# PCB_VHDCI_breakout.net
KiCad netlist of a schematic drawn in Altium Designer
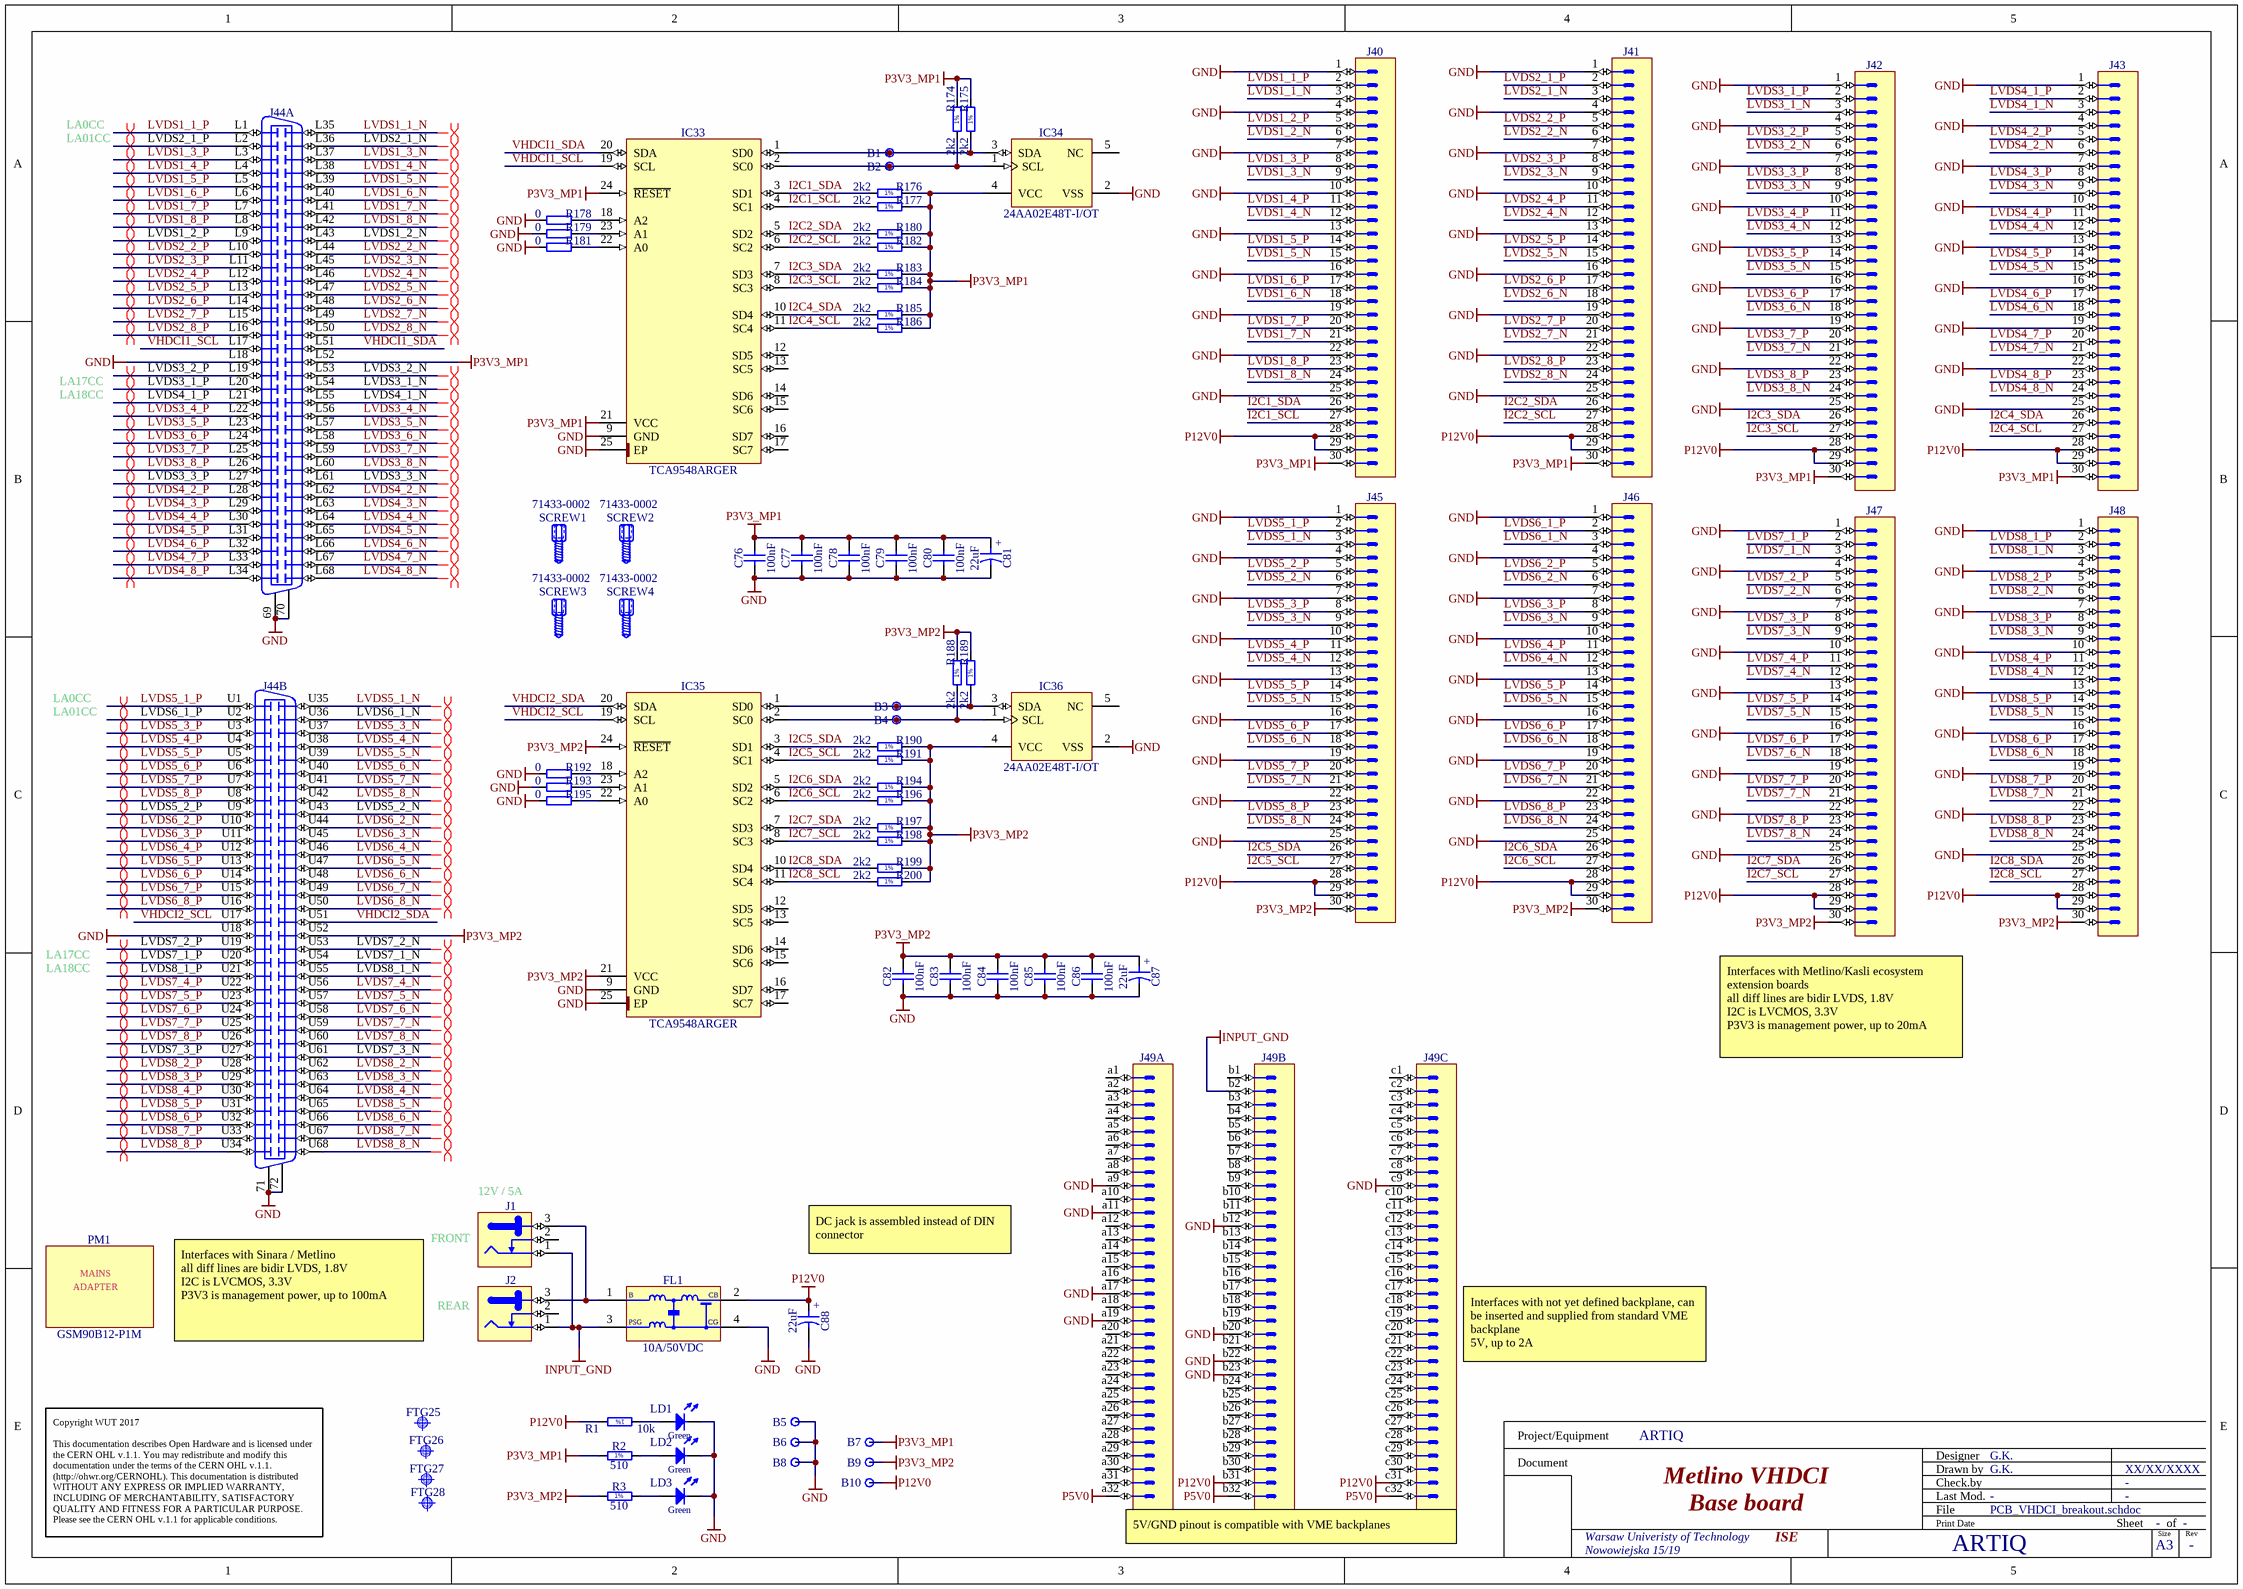
[diagram p0: PCB_VHDCI_breakout.schdoc]

(export (version "E")
  (design (tool "Eeschema 10.0.6"))
  (components
    (comp (ref "B1")
      (value "Plated Hole")
      (footprint "c130h60")
      (description "Single Terminal Socket")
      (fields (field (name "PART NUMBER") "PLATED_HOLE0.6_PAD1.3") (field (name "AUTHOR") "CERN DEM MR"))
      (libsource (lib "Eletro-mechanical") (part "Single Terminal Socket"))
    )
    (comp (ref "B2")
      (value "Plated Hole")
      (footprint "c130h60")
      (description "Single Terminal Socket")
      (fields (field (name "PART NUMBER") "PLATED_HOLE0.6_PAD1.3") (field (name "AUTHOR") "CERN DEM MR"))
      (libsource (lib "Eletro-mechanical") (part "Single Terminal Socket"))
    )
    (comp (ref "B3")
      (value "Plated Hole")
      (footprint "c130h60")
      (description "Single Terminal Socket")
      (fields (field (name "PART NUMBER") "PLATED_HOLE0.6_PAD1.3") (field (name "AUTHOR") "CERN DEM MR"))
      (libsource (lib "Eletro-mechanical") (part "Single Terminal Socket"))
    )
    (comp (ref "B4")
      (value "Plated Hole")
      (footprint "c130h60")
      (description "Single Terminal Socket")
      (fields (field (name "PART NUMBER") "PLATED_HOLE0.6_PAD1.3") (field (name "AUTHOR") "CERN DEM MR"))
      (libsource (lib "Eletro-mechanical") (part "Single Terminal Socket"))
    )
    (comp (ref "B5")
      (value "Plated Hole")
      (footprint "c130h60")
      (description "Single Terminal Socket")
      (fields (field (name "PART NUMBER") "PLATED_HOLE0.6_PAD1.3") (field (name "AUTHOR") "CERN DEM MR"))
      (libsource (lib "Eletro-mechanical") (part "Single Terminal Socket"))
    )
    (comp (ref "B6")
      (value "Plated Hole")
      (footprint "c130h60")
      (description "Single Terminal Socket")
      (fields (field (name "PART NUMBER") "PLATED_HOLE0.6_PAD1.3") (field (name "AUTHOR") "CERN DEM MR"))
      (libsource (lib "Eletro-mechanical") (part "Single Terminal Socket"))
    )
    (comp (ref "B7")
      (value "Plated Hole")
      (footprint "c130h60")
      (description "Single Terminal Socket")
      (fields (field (name "PART NUMBER") "PLATED_HOLE0.6_PAD1.3") (field (name "AUTHOR") "CERN DEM MR"))
      (libsource (lib "Eletro-mechanical") (part "Single Terminal Socket"))
    )
    (comp (ref "B8")
      (value "Plated Hole")
      (footprint "c130h60")
      (description "Single Terminal Socket")
      (fields (field (name "PART NUMBER") "PLATED_HOLE0.6_PAD1.3") (field (name "AUTHOR") "CERN DEM MR"))
      (libsource (lib "Eletro-mechanical") (part "Single Terminal Socket"))
    )
    (comp (ref "B9")
      (value "Plated Hole")
      (footprint "c130h60")
      (description "Single Terminal Socket")
      (fields (field (name "PART NUMBER") "PLATED_HOLE0.6_PAD1.3") (field (name "AUTHOR") "CERN DEM MR"))
      (libsource (lib "Eletro-mechanical") (part "Single Terminal Socket"))
    )
    (comp (ref "B10")
      (value "Plated Hole")
      (footprint "c130h60")
      (description "Single Terminal Socket")
      (fields (field (name "PART NUMBER") "PLATED_HOLE0.6_PAD1.3") (field (name "AUTHOR") "CERN DEM MR"))
      (libsource (lib "Eletro-mechanical") (part "Single Terminal Socket"))
    )
    (comp (ref "C76")
      (value "100nF")
      (footprint "CAPC1005X55N")
      (description "Non-polarised capacitor")
      (fields
        (field (name "PART NUMBER") "CC0402_100NF_16V_10%_X5R")
        (field (name "VOLTAGE") "16V")
        (field (name "AUTHOR") "CERN DEM JLC")
      )
      (libsource (lib "Capacitors") (part "Capacitor - non polarized"))
    )
    (comp (ref "C77")
      (value "100nF")
      (footprint "CAPC1005X55N")
      (description "Non-polarised capacitor")
      (fields
        (field (name "PART NUMBER") "CC0402_100NF_16V_10%_X5R")
        (field (name "VOLTAGE") "16V")
        (field (name "AUTHOR") "CERN DEM JLC")
      )
      (libsource (lib "Capacitors") (part "Capacitor - non polarized"))
    )
    (comp (ref "C78")
      (value "100nF")
      (footprint "CAPC1005X55N")
      (description "Non-polarised capacitor")
      (fields
        (field (name "PART NUMBER") "CC0402_100NF_16V_10%_X5R")
        (field (name "VOLTAGE") "16V")
        (field (name "AUTHOR") "CERN DEM JLC")
      )
      (libsource (lib "Capacitors") (part "Capacitor - non polarized"))
    )
    (comp (ref "C79")
      (value "100nF")
      (footprint "CAPC1005X55N")
      (description "Non-polarised capacitor")
      (fields
        (field (name "PART NUMBER") "CC0402_100NF_16V_10%_X5R")
        (field (name "VOLTAGE") "16V")
        (field (name "AUTHOR") "CERN DEM JLC")
      )
      (libsource (lib "Capacitors") (part "Capacitor - non polarized"))
    )
    (comp (ref "C80")
      (value "100nF")
      (footprint "CAPC1005X55N")
      (description "Non-polarised capacitor")
      (fields
        (field (name "PART NUMBER") "CC0402_100NF_16V_10%_X5R")
        (field (name "VOLTAGE") "16V")
        (field (name "AUTHOR") "CERN DEM JLC")
      )
      (libsource (lib "Capacitors") (part "Capacitor - non polarized"))
    )
    (comp (ref "C81")
      (value "22uF")
      (footprint "CAPAE530X540N")
      (description "Polarised capacitor")
      (fields
        (field (name "PART NUMBER") "CAE530-540_22UF_16V_20%")
        (field (name "VOLTAGE") "16V")
        (field (name "AUTHOR") "CERN DEM JLC")
      )
      (libsource (lib "Capacitors") (part "Capacitor - polarized"))
    )
    (comp (ref "C82")
      (value "100nF")
      (footprint "CAPC1005X55N")
      (description "Non-polarised capacitor")
      (fields
        (field (name "PART NUMBER") "CC0402_100NF_16V_10%_X5R")
        (field (name "VOLTAGE") "16V")
        (field (name "AUTHOR") "CERN DEM JLC")
      )
      (libsource (lib "Capacitors") (part "Capacitor - non polarized"))
    )
    (comp (ref "C83")
      (value "100nF")
      (footprint "CAPC1005X55N")
      (description "Non-polarised capacitor")
      (fields
        (field (name "PART NUMBER") "CC0402_100NF_16V_10%_X5R")
        (field (name "VOLTAGE") "16V")
        (field (name "AUTHOR") "CERN DEM JLC")
      )
      (libsource (lib "Capacitors") (part "Capacitor - non polarized"))
    )
    (comp (ref "C84")
      (value "100nF")
      (footprint "CAPC1005X55N")
      (description "Non-polarised capacitor")
      (fields
        (field (name "PART NUMBER") "CC0402_100NF_16V_10%_X5R")
        (field (name "VOLTAGE") "16V")
        (field (name "AUTHOR") "CERN DEM JLC")
      )
      (libsource (lib "Capacitors") (part "Capacitor - non polarized"))
    )
    (comp (ref "C85")
      (value "100nF")
      (footprint "CAPC1005X55N")
      (description "Non-polarised capacitor")
      (fields
        (field (name "PART NUMBER") "CC0402_100NF_16V_10%_X5R")
        (field (name "VOLTAGE") "16V")
        (field (name "AUTHOR") "CERN DEM JLC")
      )
      (libsource (lib "Capacitors") (part "Capacitor - non polarized"))
    )
    (comp (ref "C86")
      (value "100nF")
      (footprint "CAPC1005X55N")
      (description "Non-polarised capacitor")
      (fields
        (field (name "PART NUMBER") "CC0402_100NF_16V_10%_X5R")
        (field (name "VOLTAGE") "16V")
        (field (name "AUTHOR") "CERN DEM JLC")
      )
      (libsource (lib "Capacitors") (part "Capacitor - non polarized"))
    )
    (comp (ref "C87")
      (value "22uF")
      (footprint "CAPAE530X540N")
      (description "Polarised capacitor")
      (fields
        (field (name "PART NUMBER") "CAE530-540_22UF_16V_20%")
        (field (name "VOLTAGE") "16V")
        (field (name "AUTHOR") "CERN DEM JLC")
      )
      (libsource (lib "Capacitors") (part "Capacitor - polarized"))
    )
    (comp (ref "C88")
      (value "22uF")
      (footprint "CAPAE530X540N")
      (description "Polarised capacitor")
      (fields
        (field (name "PART NUMBER") "CAE530-540_22UF_16V_20%")
        (field (name "VOLTAGE") "16V")
        (field (name "AUTHOR") "CERN DEM JLC")
      )
      (libsource (lib "Capacitors") (part "Capacitor - polarized"))
    )
    (comp (ref "FL1")
      (value "10A/50VDC")
      (footprint "FIL_MURATA_BNX02")
      (description "Block Type EMIFIL (LC Combined)")
      (fields
        (field (name "PART NUMBER") "FIL_MURATA_BNX022-01L")
        (field (name "MANUFACTURER") "MURATA")
        (field (name "AUTHOR") "CERN DEM JLC")
      )
      (libsource (lib "Inductors & Transformers") (part "FIL_MURATA_BNX02"))
    )
    (comp (ref "FTG25")
      (value "Use only in PCB")
      (footprint "FIDUCIAL_TOP_C100-200")
      (description "Fiducial Target")
      (fields (field (name "PART NUMBER") "FIDUCIAL_TARGET_C100-200") (field (name "AUTHOR") "CERN DEM JLC"))
      (libsource (lib "Eletro-mechanical") (part "Fiducial Target"))
    )
    (comp (ref "FTG26")
      (value "Use only in PCB")
      (footprint "FIDUCIAL_TOP_S100-200")
      (description "Fiducial Target")
      (fields (field (name "PART NUMBER") "FIDUCIAL_TARGET_S100-200") (field (name "AUTHOR") "CERN DEM JLC"))
      (libsource (lib "Eletro-mechanical") (part "Fiducial Target"))
    )
    (comp (ref "FTG27")
      (value "Use only in PCB")
      (footprint "FIDUCIAL_TOP_S200-400")
      (description "Fiducial Target")
      (fields (field (name "PART NUMBER") "FIDUCIAL_TARGET_S200-400") (field (name "AUTHOR") "CERN DEM JLC"))
      (libsource (lib "Eletro-mechanical") (part "Fiducial Target"))
    )
    (comp (ref "FTG28")
      (value "Use only in PCB")
      (footprint "FIDUCIAL_TOP_S100-200")
      (description "Fiducial Target")
      (fields (field (name "PART NUMBER") "FIDUCIAL_TARGET_S100-200") (field (name "AUTHOR") "CERN DEM JLC"))
      (libsource (lib "Eletro-mechanical") (part "Fiducial Target"))
    )
    (comp (ref "IC33")
      (value "TCA9548ARGER")
      (footprint "QFN50P400X400X100-25N-S220")
      (description "Low Voltage 8-Channel I2C Switch With Reset")
      (fields (field (name "MANUFACTURER") "TEXAS INSTRUMENTS") (field (name "AUTHOR") "CERN DEM JLC"))
      (libsource (lib "ICs And Semiconductors") (part "TCA9548ARGER"))
    )
    (comp (ref "IC34")
      (value "24AA02E48T-I/OT")
      (footprint "SOT95P280X145-5N")
      (description "1.7V-5.5V, 2K I2C Serial EEPROM With EUI-48 Node Identity")
      (fields (field (name "MANUFACTURER") "MICROCHIP TECHNOLOGY") (field (name "AUTHOR") "CERN DEM MR"))
      (libsource (lib "ICs And Semiconductors") (part "24AA02E48T-I/OT"))
    )
    (comp (ref "IC35")
      (value "TCA9548ARGER")
      (footprint "QFN50P400X400X100-25N-S220")
      (description "Low Voltage 8-Channel I2C Switch With Reset")
      (fields (field (name "MANUFACTURER") "TEXAS INSTRUMENTS") (field (name "AUTHOR") "CERN DEM JLC"))
      (libsource (lib "ICs And Semiconductors") (part "TCA9548ARGER"))
    )
    (comp (ref "IC36")
      (value "24AA02E48T-I/OT")
      (footprint "SOT95P280X145-5N")
      (description "1.7V-5.5V, 2K I2C Serial EEPROM With EUI-48 Node Identity")
      (fields (field (name "MANUFACTURER") "MICROCHIP TECHNOLOGY") (field (name "AUTHOR") "CERN DEM MR"))
      (libsource (lib "ICs And Semiconductors") (part "24AA02E48T-I/OT"))
    )
    (comp (ref "J1")
      (value "Jack")
      (footprint "SWITCHCRAFT_L712RA")
      (description "24V /3. 5A, 2.1mm Diameter Pin, SMD DC Power Supply Connector With  Break Contact")
      (fields
        (field (name "PART NUMBER") "SWITCHCRAFT_L712RA")
        (field (name "MANUFACTURER") "SWITCHCRAFT")
        (field (name "AUTHOR") "GK")
      )
      (libsource (lib "LIBRARY_SCH") (part "CON_DC_5A_THT_RA"))
    )
    (comp (ref "J2")
      (value "Jack")
      (footprint "SWITCHCRAFT_L712RA")
      (description "24V /3. 5A, 2.1mm Diameter Pin, SMD DC Power Supply Connector With  Break Contact")
      (fields
        (field (name "PART NUMBER") "SWITCHCRAFT_L712RA")
        (field (name "MANUFACTURER") "SWITCHCRAFT")
        (field (name "AUTHOR") "GK")
      )
      (libsource (lib "LIBRARY_SCH") (part "CON_DC_5A_THT_RA"))
    )
    (comp (ref "J40")
      (value "~")
      (footprint "3M_N2530-6002RB")
      (description "Connector 30 Male")
      (fields
        (field (name "PART NUMBER") "3M_N2530-6002RB")
        (field (name "MANUFACTURER") "3M")
        (field (name "AUTHOR") "CERN DEM JLC")
      )
      (libsource (lib "Connectors") (part "Connector 30 Male"))
    )
    (comp (ref "J41")
      (value "~")
      (footprint "3M_N2530-6002RB")
      (description "Connector 30 Male")
      (fields
        (field (name "PART NUMBER") "3M_N2530-6002RB")
        (field (name "MANUFACTURER") "3M")
        (field (name "AUTHOR") "CERN DEM JLC")
      )
      (libsource (lib "Connectors") (part "Connector 30 Male"))
    )
    (comp (ref "J42")
      (value "~")
      (footprint "3M_N2530-6002RB")
      (description "Connector 30 Male")
      (fields
        (field (name "PART NUMBER") "3M_N2530-6002RB")
        (field (name "MANUFACTURER") "3M")
        (field (name "AUTHOR") "CERN DEM JLC")
      )
      (libsource (lib "Connectors") (part "Connector 30 Male"))
    )
    (comp (ref "J43")
      (value "~")
      (footprint "3M_N2530-6002RB")
      (description "Connector 30 Male")
      (fields
        (field (name "PART NUMBER") "3M_N2530-6002RB")
        (field (name "MANUFACTURER") "3M")
        (field (name "AUTHOR") "CERN DEM JLC")
      )
      (libsource (lib "Connectors") (part "Connector 30 Male"))
    )
    (comp (ref "J44")
      (value "VHDCI")
      (footprint "MOLEX_74337-0015")
      (description "Very High Density Cable Interconnect (VHDCI ) 2x68 Female")
      (fields
        (field (name "PART NUMBER") "Delivered by GK")
        (field (name "MANUFACTURER") "MOLEX")
        (field (name "AUTHOR") "CERN DEM JLC")
      )
      (libsource (lib "Connectors") (part "Connector VHDCI 2x68 Female"))
    )
    (comp (ref "J45")
      (value "~")
      (footprint "3M_N2530-6002RB")
      (description "Connector 30 Male")
      (fields
        (field (name "PART NUMBER") "3M_N2530-6002RB")
        (field (name "MANUFACTURER") "3M")
        (field (name "AUTHOR") "CERN DEM JLC")
      )
      (libsource (lib "Connectors") (part "Connector 30 Male"))
    )
    (comp (ref "J46")
      (value "~")
      (footprint "3M_N2530-6002RB")
      (description "Connector 30 Male")
      (fields
        (field (name "PART NUMBER") "3M_N2530-6002RB")
        (field (name "MANUFACTURER") "3M")
        (field (name "AUTHOR") "CERN DEM JLC")
      )
      (libsource (lib "Connectors") (part "Connector 30 Male"))
    )
    (comp (ref "J47")
      (value "~")
      (footprint "3M_N2530-6002RB")
      (description "Connector 30 Male")
      (fields
        (field (name "PART NUMBER") "3M_N2530-6002RB")
        (field (name "MANUFACTURER") "3M")
        (field (name "AUTHOR") "CERN DEM JLC")
      )
      (libsource (lib "Connectors") (part "Connector 30 Male"))
    )
    (comp (ref "J48")
      (value "~")
      (footprint "3M_N2530-6002RB")
      (description "Connector 30 Male")
      (fields
        (field (name "PART NUMBER") "3M_N2530-6002RB")
        (field (name "MANUFACTURER") "3M")
        (field (name "AUTHOR") "CERN DEM JLC")
      )
      (libsource (lib "Connectors") (part "Connector 30 Male"))
    )
    (comp (ref "J49")
      (value "DNP")
      (footprint "HARTING_09 03 196 2921")
      (description "Connector 96abc male (3x32)")
      (fields
        (field (name "PART NUMBER") "HARTING_09 03 196 2921")
        (field (name "MANUFACTURER") "HARTING")
        (field (name "AUTHOR") "CERN DEM JLC")
      )
      (libsource (lib "Connectors") (part "Connector 96abc male (3x32)"))
    )
    (comp (ref "LD1")
      (value "Green")
      (footprint "LED_KINGBRIGHT_KPH-1608CGCK")
      (description "LED Green 1C 2A")
      (fields
        (field (name "PART NUMBER") "LED_KINGBRIGHT_KPH-1608CGCK")
        (field (name "MANUFACTURER") "KINGBRIGHT")
        (field (name "AUTHOR") "CERN DEM JLC")
      )
      (libsource (lib "ICs And Semiconductors") (part "LED Green 1C 2A"))
    )
    (comp (ref "LD2")
      (value "Green")
      (footprint "LED_KINGBRIGHT_KPH-1608CGCK")
      (description "LED Green 1C 2A")
      (fields
        (field (name "PART NUMBER") "LED_KINGBRIGHT_KPH-1608CGCK")
        (field (name "MANUFACTURER") "KINGBRIGHT")
        (field (name "AUTHOR") "CERN DEM JLC")
      )
      (libsource (lib "ICs And Semiconductors") (part "LED Green 1C 2A"))
    )
    (comp (ref "LD3")
      (value "Green")
      (footprint "LED_KINGBRIGHT_KPH-1608CGCK")
      (description "LED Green 1C 2A")
      (fields
        (field (name "PART NUMBER") "LED_KINGBRIGHT_KPH-1608CGCK")
        (field (name "MANUFACTURER") "KINGBRIGHT")
        (field (name "AUTHOR") "CERN DEM JLC")
      )
      (libsource (lib "ICs And Semiconductors") (part "LED Green 1C 2A"))
    )
    (comp (ref "PM1")
      (value "GSM90B12-P1M")
      (footprint "DC_DC_GSM90B12-P1M")
      (description "90W  AC-DC  Medical Power Adaptor")
      (fields (field (name "MANUFACTURER") "MEAN WELL") (field (name "AUTHOR") "GK"))
      (libsource (lib "LIBRARY_SCH") (part "DC_DC_GSM90B12-P1M"))
    )
    (comp (ref "R1")
      (value "10k")
      (footprint "RESC1005X40N")
      (description "Resistor - 1%")
      (fields
        (field (name "PART NUMBER") "R0402_10K_1%_0.0625W_100PPM")
        (field (name "POWER") "0.0625W")
        (field (name "AUTHOR") "CERN DEM JLC")
      )
      (libsource (lib "Resistors") (part "Resistor - 1%"))
    )
    (comp (ref "R2")
      (value "510")
      (footprint "RESC1005X40N")
      (description "Resistor - 1%")
      (fields
        (field (name "PART NUMBER") "R0402_510R_1%_0.0625W_100PPM")
        (field (name "POWER") "0.0625W")
        (field (name "AUTHOR") "CERN DEM JLC")
      )
      (libsource (lib "Resistors") (part "Resistor - 1%"))
    )
    (comp (ref "R3")
      (value "510")
      (footprint "RESC1005X40N")
      (description "Resistor - 1%")
      (fields
        (field (name "PART NUMBER") "R0402_510R_1%_0.0625W_100PPM")
        (field (name "POWER") "0.0625W")
        (field (name "AUTHOR") "CERN DEM JLC")
      )
      (libsource (lib "Resistors") (part "Resistor - 1%"))
    )
    (comp (ref "R174")
      (value "2k2")
      (footprint "RESC1005X40N")
      (description "Resistor - 1%")
      (fields
        (field (name "PART NUMBER") "R0402_2K2_1%_0.0625W_100PPM")
        (field (name "POWER") "0.0625W")
        (field (name "AUTHOR") "CERN DEM JLC")
      )
      (libsource (lib "Resistors") (part "Resistor - 1%"))
    )
    (comp (ref "R175")
      (value "2k2")
      (footprint "RESC1005X40N")
      (description "Resistor - 1%")
      (fields
        (field (name "PART NUMBER") "R0402_2K2_1%_0.0625W_100PPM")
        (field (name "POWER") "0.0625W")
        (field (name "AUTHOR") "CERN DEM JLC")
      )
      (libsource (lib "Resistors") (part "Resistor - 1%"))
    )
    (comp (ref "R176")
      (value "2k2")
      (footprint "RESC1005X40N")
      (description "Resistor - 1%")
      (fields
        (field (name "PART NUMBER") "R0402_2K2_1%_0.0625W_100PPM")
        (field (name "POWER") "0.0625W")
        (field (name "AUTHOR") "CERN DEM JLC")
      )
      (libsource (lib "Resistors") (part "Resistor - 1%"))
    )
    (comp (ref "R177")
      (value "2k2")
      (footprint "RESC1005X40N")
      (description "Resistor - 1%")
      (fields
        (field (name "PART NUMBER") "R0402_2K2_1%_0.0625W_100PPM")
        (field (name "POWER") "0.0625W")
        (field (name "AUTHOR") "CERN DEM JLC")
      )
      (libsource (lib "Resistors") (part "Resistor - 1%"))
    )
    (comp (ref "R178")
      (value "0")
      (footprint "RESC1005X40N")
      (description "Resistor")
      (fields
        (field (name "PART NUMBER") "R0402_0R_JUMPER")
        (field (name "MANUFACTURER") "GENERIC")
        (field (name "AUTHOR") "CERN DEM JLC")
      )
      (libsource (lib "Resistors") (part "Resistor"))
    )
    (comp (ref "R179")
      (value "0")
      (footprint "RESC1005X40N")
      (description "Resistor")
      (fields
        (field (name "PART NUMBER") "R0402_0R_JUMPER")
        (field (name "MANUFACTURER") "GENERIC")
        (field (name "AUTHOR") "CERN DEM JLC")
      )
      (libsource (lib "Resistors") (part "Resistor"))
    )
    (comp (ref "R180")
      (value "2k2")
      (footprint "RESC1005X40N")
      (description "Resistor - 1%")
      (fields
        (field (name "PART NUMBER") "R0402_2K2_1%_0.0625W_100PPM")
        (field (name "POWER") "0.0625W")
        (field (name "AUTHOR") "CERN DEM JLC")
      )
      (libsource (lib "Resistors") (part "Resistor - 1%"))
    )
    (comp (ref "R181")
      (value "0")
      (footprint "RESC1005X40N")
      (description "Resistor")
      (fields
        (field (name "PART NUMBER") "R0402_0R_JUMPER")
        (field (name "MANUFACTURER") "GENERIC")
        (field (name "AUTHOR") "CERN DEM JLC")
      )
      (libsource (lib "Resistors") (part "Resistor"))
    )
    (comp (ref "R182")
      (value "2k2")
      (footprint "RESC1005X40N")
      (description "Resistor - 1%")
      (fields
        (field (name "PART NUMBER") "R0402_2K2_1%_0.0625W_100PPM")
        (field (name "POWER") "0.0625W")
        (field (name "AUTHOR") "CERN DEM JLC")
      )
      (libsource (lib "Resistors") (part "Resistor - 1%"))
    )
    (comp (ref "R183")
      (value "2k2")
      (footprint "RESC1005X40N")
      (description "Resistor - 1%")
      (fields
        (field (name "PART NUMBER") "R0402_2K2_1%_0.0625W_100PPM")
        (field (name "POWER") "0.0625W")
        (field (name "AUTHOR") "CERN DEM JLC")
      )
      (libsource (lib "Resistors") (part "Resistor - 1%"))
    )
    (comp (ref "R184")
      (value "2k2")
      (footprint "RESC1005X40N")
      (description "Resistor - 1%")
      (fields
        (field (name "PART NUMBER") "R0402_2K2_1%_0.0625W_100PPM")
        (field (name "POWER") "0.0625W")
        (field (name "AUTHOR") "CERN DEM JLC")
      )
      (libsource (lib "Resistors") (part "Resistor - 1%"))
    )
    (comp (ref "R185")
      (value "2k2")
      (footprint "RESC1005X40N")
      (description "Resistor - 1%")
      (fields
        (field (name "PART NUMBER") "R0402_2K2_1%_0.0625W_100PPM")
        (field (name "POWER") "0.0625W")
        (field (name "AUTHOR") "CERN DEM JLC")
      )
      (libsource (lib "Resistors") (part "Resistor - 1%"))
    )
    (comp (ref "R186")
      (value "2k2")
      (footprint "RESC1005X40N")
      (description "Resistor - 1%")
      (fields
        (field (name "PART NUMBER") "R0402_2K2_1%_0.0625W_100PPM")
        (field (name "POWER") "0.0625W")
        (field (name "AUTHOR") "CERN DEM JLC")
      )
      (libsource (lib "Resistors") (part "Resistor - 1%"))
    )
    (comp (ref "R188")
      (value "2k2")
      (footprint "RESC1005X40N")
      (description "Resistor - 1%")
      (fields
        (field (name "PART NUMBER") "R0402_2K2_1%_0.0625W_100PPM")
        (field (name "POWER") "0.0625W")
        (field (name "AUTHOR") "CERN DEM JLC")
      )
      (libsource (lib "Resistors") (part "Resistor - 1%"))
    )
    (comp (ref "R189")
      (value "2k2")
      (footprint "RESC1005X40N")
      (description "Resistor - 1%")
      (fields
        (field (name "PART NUMBER") "R0402_2K2_1%_0.0625W_100PPM")
        (field (name "POWER") "0.0625W")
        (field (name "AUTHOR") "CERN DEM JLC")
      )
      (libsource (lib "Resistors") (part "Resistor - 1%"))
    )
    (comp (ref "R190")
      (value "2k2")
      (footprint "RESC1005X40N")
      (description "Resistor - 1%")
      (fields
        (field (name "PART NUMBER") "R0402_2K2_1%_0.0625W_100PPM")
        (field (name "POWER") "0.0625W")
        (field (name "AUTHOR") "CERN DEM JLC")
      )
      (libsource (lib "Resistors") (part "Resistor - 1%"))
    )
    (comp (ref "R191")
      (value "2k2")
      (footprint "RESC1005X40N")
      (description "Resistor - 1%")
      (fields
        (field (name "PART NUMBER") "R0402_2K2_1%_0.0625W_100PPM")
        (field (name "POWER") "0.0625W")
        (field (name "AUTHOR") "CERN DEM JLC")
      )
      (libsource (lib "Resistors") (part "Resistor - 1%"))
    )
    (comp (ref "R192")
      (value "0")
      (footprint "RESC1005X40N")
      (description "Resistor")
      (fields
        (field (name "PART NUMBER") "R0402_0R_JUMPER")
        (field (name "MANUFACTURER") "GENERIC")
        (field (name "AUTHOR") "CERN DEM JLC")
      )
      (libsource (lib "Resistors") (part "Resistor"))
    )
    (comp (ref "R193")
      (value "0")
      (footprint "RESC1005X40N")
      (description "Resistor")
      (fields
        (field (name "PART NUMBER") "R0402_0R_JUMPER")
        (field (name "MANUFACTURER") "GENERIC")
        (field (name "AUTHOR") "CERN DEM JLC")
      )
      (libsource (lib "Resistors") (part "Resistor"))
    )
    (comp (ref "R194")
      (value "2k2")
      (footprint "RESC1005X40N")
      (description "Resistor - 1%")
      (fields
        (field (name "PART NUMBER") "R0402_2K2_1%_0.0625W_100PPM")
        (field (name "POWER") "0.0625W")
        (field (name "AUTHOR") "CERN DEM JLC")
      )
      (libsource (lib "Resistors") (part "Resistor - 1%"))
    )
    (comp (ref "R195")
      (value "0")
      (footprint "RESC1005X40N")
      (description "Resistor")
      (fields
        (field (name "PART NUMBER") "R0402_0R_JUMPER")
        (field (name "MANUFACTURER") "GENERIC")
        (field (name "AUTHOR") "CERN DEM JLC")
      )
      (libsource (lib "Resistors") (part "Resistor"))
    )
    (comp (ref "R196")
      (value "2k2")
      (footprint "RESC1005X40N")
      (description "Resistor - 1%")
      (fields
        (field (name "PART NUMBER") "R0402_2K2_1%_0.0625W_100PPM")
        (field (name "POWER") "0.0625W")
        (field (name "AUTHOR") "CERN DEM JLC")
      )
      (libsource (lib "Resistors") (part "Resistor - 1%"))
    )
    (comp (ref "R197")
      (value "2k2")
      (footprint "RESC1005X40N")
      (description "Resistor - 1%")
      (fields
        (field (name "PART NUMBER") "R0402_2K2_1%_0.0625W_100PPM")
        (field (name "POWER") "0.0625W")
        (field (name "AUTHOR") "CERN DEM JLC")
      )
      (libsource (lib "Resistors") (part "Resistor - 1%"))
    )
    (comp (ref "R198")
      (value "2k2")
      (footprint "RESC1005X40N")
      (description "Resistor - 1%")
      (fields
        (field (name "PART NUMBER") "R0402_2K2_1%_0.0625W_100PPM")
        (field (name "POWER") "0.0625W")
        (field (name "AUTHOR") "CERN DEM JLC")
      )
      (libsource (lib "Resistors") (part "Resistor - 1%"))
    )
    (comp (ref "R199")
      (value "2k2")
      (footprint "RESC1005X40N")
      (description "Resistor - 1%")
      (fields
        (field (name "PART NUMBER") "R0402_2K2_1%_0.0625W_100PPM")
        (field (name "POWER") "0.0625W")
        (field (name "AUTHOR") "CERN DEM JLC")
      )
      (libsource (lib "Resistors") (part "Resistor - 1%"))
    )
    (comp (ref "R200")
      (value "2k2")
      (footprint "RESC1005X40N")
      (description "Resistor - 1%")
      (fields
        (field (name "PART NUMBER") "R0402_2K2_1%_0.0625W_100PPM")
        (field (name "POWER") "0.0625W")
        (field (name "AUTHOR") "CERN DEM JLC")
      )
      (libsource (lib "Resistors") (part "Resistor - 1%"))
    )
    (comp (ref "SCREW1")
      (value "71433-0002")
      (footprint "MOLEX_71433-0002")
      (description "VHDCI Female Screw Lock")
      (fields
        (field (name "PART NUMBER") "MOLEX_71433-0002")
        (field (name "MANUFACTURER") "Molex")
        (field (name "AUTHOR") "GK")
      )
      (libsource (lib "LIBRARY_SCH") (part "MECH_VHDCI_screw_lock"))
    )
    (comp (ref "SCREW2")
      (value "71433-0002")
      (footprint "MOLEX_71433-0002")
      (description "VHDCI Female Screw Lock")
      (fields
        (field (name "PART NUMBER") "MOLEX_71433-0002")
        (field (name "MANUFACTURER") "Molex")
        (field (name "AUTHOR") "GK")
      )
      (libsource (lib "LIBRARY_SCH") (part "MECH_VHDCI_screw_lock"))
    )
    (comp (ref "SCREW3")
      (value "71433-0002")
      (footprint "MOLEX_71433-0002")
      (description "VHDCI Female Screw Lock")
      (fields
        (field (name "PART NUMBER") "MOLEX_71433-0002")
        (field (name "MANUFACTURER") "Molex")
        (field (name "AUTHOR") "GK")
      )
      (libsource (lib "LIBRARY_SCH") (part "MECH_VHDCI_screw_lock"))
    )
    (comp (ref "SCREW4")
      (value "71433-0002")
      (footprint "MOLEX_71433-0002")
      (description "VHDCI Female Screw Lock")
      (fields
        (field (name "PART NUMBER") "MOLEX_71433-0002")
        (field (name "MANUFACTURER") "Molex")
        (field (name "AUTHOR") "GK")
      )
      (libsource (lib "LIBRARY_SCH") (part "MECH_VHDCI_screw_lock"))
    )
  )
  (nets
    (net (code "1") (name "/I2C1_SCL") (class "Default")
      (node (ref "IC33") (pin "4") (pinfunction "SC1_4") (pintype "bidirectional"))
      (node (ref "J40") (pin "27") (pinfunction "27_27") (pintype "bidirectional"))
      (node (ref "R177") (pin "1") (pinfunction "1_1") (pintype "passive"))
    )
    (net (code "2") (name "/I2C1_SDA") (class "Default")
      (node (ref "IC33") (pin "3") (pinfunction "SD1_3") (pintype "bidirectional"))
      (node (ref "J40") (pin "26") (pinfunction "26_26") (pintype "bidirectional"))
      (node (ref "R176") (pin "1") (pinfunction "1_1") (pintype "passive"))
    )
    (net (code "3") (name "/I2C2_SCL") (class "Default")
      (node (ref "IC33") (pin "6") (pinfunction "SC2_6") (pintype "bidirectional"))
      (node (ref "J41") (pin "27") (pinfunction "27_27") (pintype "bidirectional"))
      (node (ref "R182") (pin "1") (pinfunction "1_1") (pintype "passive"))
    )
    (net (code "4") (name "/I2C2_SDA") (class "Default")
      (node (ref "IC33") (pin "5") (pinfunction "SD2_5") (pintype "bidirectional"))
      (node (ref "J41") (pin "26") (pinfunction "26_26") (pintype "bidirectional"))
      (node (ref "R180") (pin "1") (pinfunction "1_1") (pintype "passive"))
    )
    (net (code "5") (name "/I2C3_SCL") (class "Default")
      (node (ref "IC33") (pin "8") (pinfunction "SC3_8") (pintype "bidirectional"))
      (node (ref "J42") (pin "27") (pinfunction "27_27") (pintype "bidirectional"))
      (node (ref "R184") (pin "1") (pinfunction "1_1") (pintype "passive"))
    )
    (net (code "6") (name "/I2C3_SDA") (class "Default")
      (node (ref "IC33") (pin "7") (pinfunction "SD3_7") (pintype "bidirectional"))
      (node (ref "J42") (pin "26") (pinfunction "26_26") (pintype "bidirectional"))
      (node (ref "R183") (pin "1") (pinfunction "1_1") (pintype "passive"))
    )
    (net (code "7") (name "/I2C4_SCL") (class "Default")
      (node (ref "IC33") (pin "11") (pinfunction "SC4_11") (pintype "bidirectional"))
      (node (ref "J43") (pin "27") (pinfunction "27_27") (pintype "bidirectional"))
      (node (ref "R186") (pin "1") (pinfunction "1_1") (pintype "passive"))
    )
    (net (code "8") (name "/I2C4_SDA") (class "Default")
      (node (ref "IC33") (pin "10") (pinfunction "SD4_10") (pintype "bidirectional"))
      (node (ref "J43") (pin "26") (pinfunction "26_26") (pintype "bidirectional"))
      (node (ref "R185") (pin "1") (pinfunction "1_1") (pintype "passive"))
    )
    (net (code "9") (name "/I2C5_SCL") (class "Default")
      (node (ref "IC35") (pin "4") (pinfunction "SC1_4") (pintype "bidirectional"))
      (node (ref "J45") (pin "27") (pinfunction "27_27") (pintype "bidirectional"))
      (node (ref "R191") (pin "1") (pinfunction "1_1") (pintype "passive"))
    )
    (net (code "10") (name "/I2C5_SDA") (class "Default")
      (node (ref "IC35") (pin "3") (pinfunction "SD1_3") (pintype "bidirectional"))
      (node (ref "J45") (pin "26") (pinfunction "26_26") (pintype "bidirectional"))
      (node (ref "R190") (pin "1") (pinfunction "1_1") (pintype "passive"))
    )
    (net (code "11") (name "/I2C6_SCL") (class "Default")
      (node (ref "IC35") (pin "6") (pinfunction "SC2_6") (pintype "bidirectional"))
      (node (ref "J46") (pin "27") (pinfunction "27_27") (pintype "bidirectional"))
      (node (ref "R196") (pin "1") (pinfunction "1_1") (pintype "passive"))
    )
    (net (code "12") (name "/I2C6_SDA") (class "Default")
      (node (ref "IC35") (pin "5") (pinfunction "SD2_5") (pintype "bidirectional"))
      (node (ref "J46") (pin "26") (pinfunction "26_26") (pintype "bidirectional"))
      (node (ref "R194") (pin "1") (pinfunction "1_1") (pintype "passive"))
    )
    (net (code "13") (name "/I2C7_SCL") (class "Default")
      (node (ref "IC35") (pin "8") (pinfunction "SC3_8") (pintype "bidirectional"))
      (node (ref "J47") (pin "27") (pinfunction "27_27") (pintype "bidirectional"))
      (node (ref "R198") (pin "1") (pinfunction "1_1") (pintype "passive"))
    )
    (net (code "14") (name "/I2C7_SDA") (class "Default")
      (node (ref "IC35") (pin "7") (pinfunction "SD3_7") (pintype "bidirectional"))
      (node (ref "J47") (pin "26") (pinfunction "26_26") (pintype "bidirectional"))
      (node (ref "R197") (pin "1") (pinfunction "1_1") (pintype "passive"))
    )
    (net (code "15") (name "/I2C8_SCL") (class "Default")
      (node (ref "IC35") (pin "11") (pinfunction "SC4_11") (pintype "bidirectional"))
      (node (ref "J48") (pin "27") (pinfunction "27_27") (pintype "bidirectional"))
      (node (ref "R200") (pin "1") (pinfunction "1_1") (pintype "passive"))
    )
    (net (code "16") (name "/I2C8_SDA") (class "Default")
      (node (ref "IC35") (pin "10") (pinfunction "SD4_10") (pintype "bidirectional"))
      (node (ref "J48") (pin "26") (pinfunction "26_26") (pintype "bidirectional"))
      (node (ref "R199") (pin "1") (pinfunction "1_1") (pintype "passive"))
    )
    (net (code "17") (name "/LVDS1_1_N") (class "Default")
      (node (ref "J40") (pin "3") (pinfunction "3_3") (pintype "bidirectional"))
      (node (ref "J44") (pin "L35") (pinfunction "35_L35") (pintype "bidirectional"))
    )
    (net (code "18") (name "/LVDS1_1_P") (class "Default")
      (node (ref "J40") (pin "2") (pinfunction "2_2") (pintype "bidirectional"))
      (node (ref "J44") (pin "L1") (pinfunction "1_L1") (pintype "bidirectional"))
    )
    (net (code "19") (name "/LVDS1_2_N") (class "Default")
      (node (ref "J40") (pin "6") (pinfunction "6_6") (pintype "bidirectional"))
      (node (ref "J44") (pin "L43") (pinfunction "43_L43") (pintype "bidirectional"))
    )
    (net (code "20") (name "/LVDS1_2_P") (class "Default")
      (node (ref "J40") (pin "5") (pinfunction "5_5") (pintype "bidirectional"))
      (node (ref "J44") (pin "L9") (pinfunction "9_L9") (pintype "bidirectional"))
    )
    (net (code "21") (name "/LVDS1_3_N") (class "Default")
      (node (ref "J40") (pin "9") (pinfunction "9_9") (pintype "bidirectional"))
      (node (ref "J44") (pin "L37") (pinfunction "37_L37") (pintype "bidirectional"))
    )
    (net (code "22") (name "/LVDS1_3_P") (class "Default")
      (node (ref "J40") (pin "8") (pinfunction "8_8") (pintype "bidirectional"))
      (node (ref "J44") (pin "L3") (pinfunction "3_L3") (pintype "bidirectional"))
    )
    (net (code "23") (name "/LVDS1_4_N") (class "Default")
      (node (ref "J40") (pin "12") (pinfunction "12_12") (pintype "bidirectional"))
      (node (ref "J44") (pin "L38") (pinfunction "38_L38") (pintype "bidirectional"))
    )
    (net (code "24") (name "/LVDS1_4_P") (class "Default")
      (node (ref "J40") (pin "11") (pinfunction "11_11") (pintype "bidirectional"))
      (node (ref "J44") (pin "L4") (pinfunction "4_L4") (pintype "bidirectional"))
    )
    (net (code "25") (name "/LVDS1_5_N") (class "Default")
      (node (ref "J40") (pin "15") (pinfunction "15_15") (pintype "bidirectional"))
      (node (ref "J44") (pin "L39") (pinfunction "39_L39") (pintype "bidirectional"))
    )
    (net (code "26") (name "/LVDS1_5_P") (class "Default")
      (node (ref "J40") (pin "14") (pinfunction "14_14") (pintype "bidirectional"))
      (node (ref "J44") (pin "L5") (pinfunction "5_L5") (pintype "bidirectional"))
    )
    (net (code "27") (name "/LVDS1_6_N") (class "Default")
      (node (ref "J40") (pin "18") (pinfunction "18_18") (pintype "bidirectional"))
      (node (ref "J44") (pin "L40") (pinfunction "40_L40") (pintype "bidirectional"))
    )
    (net (code "28") (name "/LVDS1_6_P") (class "Default")
      (node (ref "J40") (pin "17") (pinfunction "17_17") (pintype "bidirectional"))
      (node (ref "J44") (pin "L6") (pinfunction "6_L6") (pintype "bidirectional"))
    )
    (net (code "29") (name "/LVDS1_7_N") (class "Default")
      (node (ref "J40") (pin "21") (pinfunction "21_21") (pintype "bidirectional"))
      (node (ref "J44") (pin "L41") (pinfunction "41_L41") (pintype "bidirectional"))
    )
    (net (code "30") (name "/LVDS1_7_P") (class "Default")
      (node (ref "J40") (pin "20") (pinfunction "20_20") (pintype "bidirectional"))
      (node (ref "J44") (pin "L7") (pinfunction "7_L7") (pintype "bidirectional"))
    )
    (net (code "31") (name "/LVDS1_8_N") (class "Default")
      (node (ref "J40") (pin "24") (pinfunction "24_24") (pintype "bidirectional"))
      (node (ref "J44") (pin "L42") (pinfunction "42_L42") (pintype "bidirectional"))
    )
    (net (code "32") (name "/LVDS1_8_P") (class "Default")
      (node (ref "J40") (pin "23") (pinfunction "23_23") (pintype "bidirectional"))
      (node (ref "J44") (pin "L8") (pinfunction "8_L8") (pintype "bidirectional"))
    )
    (net (code "33") (name "/LVDS2_1_N") (class "Default")
      (node (ref "J41") (pin "3") (pinfunction "3_3") (pintype "bidirectional"))
      (node (ref "J44") (pin "L36") (pinfunction "36_L36") (pintype "bidirectional"))
    )
    (net (code "34") (name "/LVDS2_1_P") (class "Default")
      (node (ref "J41") (pin "2") (pinfunction "2_2") (pintype "bidirectional"))
      (node (ref "J44") (pin "L2") (pinfunction "2_L2") (pintype "bidirectional"))
    )
    (net (code "35") (name "/LVDS2_2_N") (class "Default")
      (node (ref "J41") (pin "6") (pinfunction "6_6") (pintype "bidirectional"))
      (node (ref "J44") (pin "L44") (pinfunction "44_L44") (pintype "bidirectional"))
    )
    (net (code "36") (name "/LVDS2_2_P") (class "Default")
      (node (ref "J41") (pin "5") (pinfunction "5_5") (pintype "bidirectional"))
      (node (ref "J44") (pin "L10") (pinfunction "10_L10") (pintype "bidirectional"))
    )
    (net (code "37") (name "/LVDS2_3_N") (class "Default")
      (node (ref "J41") (pin "9") (pinfunction "9_9") (pintype "bidirectional"))
      (node (ref "J44") (pin "L45") (pinfunction "45_L45") (pintype "bidirectional"))
    )
    (net (code "38") (name "/LVDS2_3_P") (class "Default")
      (node (ref "J41") (pin "8") (pinfunction "8_8") (pintype "bidirectional"))
      (node (ref "J44") (pin "L11") (pinfunction "11_L11") (pintype "bidirectional"))
    )
    (net (code "39") (name "/LVDS2_4_N") (class "Default")
      (node (ref "J41") (pin "12") (pinfunction "12_12") (pintype "bidirectional"))
      (node (ref "J44") (pin "L46") (pinfunction "46_L46") (pintype "bidirectional"))
    )
    (net (code "40") (name "/LVDS2_4_P") (class "Default")
      (node (ref "J41") (pin "11") (pinfunction "11_11") (pintype "bidirectional"))
      (node (ref "J44") (pin "L12") (pinfunction "12_L12") (pintype "bidirectional"))
    )
    (net (code "41") (name "/LVDS2_5_N") (class "Default")
      (node (ref "J41") (pin "15") (pinfunction "15_15") (pintype "bidirectional"))
      (node (ref "J44") (pin "L47") (pinfunction "47_L47") (pintype "bidirectional"))
    )
    (net (code "42") (name "/LVDS2_5_P") (class "Default")
      (node (ref "J41") (pin "14") (pinfunction "14_14") (pintype "bidirectional"))
      (node (ref "J44") (pin "L13") (pinfunction "13_L13") (pintype "bidirectional"))
    )
    (net (code "43") (name "/LVDS2_6_N") (class "Default")
      (node (ref "J41") (pin "18") (pinfunction "18_18") (pintype "bidirectional"))
      (node (ref "J44") (pin "L48") (pinfunction "48_L48") (pintype "bidirectional"))
    )
    (net (code "44") (name "/LVDS2_6_P") (class "Default")
      (node (ref "J41") (pin "17") (pinfunction "17_17") (pintype "bidirectional"))
      (node (ref "J44") (pin "L14") (pinfunction "14_L14") (pintype "bidirectional"))
    )
    (net (code "45") (name "/LVDS2_7_N") (class "Default")
      (node (ref "J41") (pin "21") (pinfunction "21_21") (pintype "bidirectional"))
      (node (ref "J44") (pin "L49") (pinfunction "49_L49") (pintype "bidirectional"))
    )
    (net (code "46") (name "/LVDS2_7_P") (class "Default")
      (node (ref "J41") (pin "20") (pinfunction "20_20") (pintype "bidirectional"))
      (node (ref "J44") (pin "L15") (pinfunction "15_L15") (pintype "bidirectional"))
    )
    (net (code "47") (name "/LVDS2_8_N") (class "Default")
      (node (ref "J41") (pin "24") (pinfunction "24_24") (pintype "bidirectional"))
      (node (ref "J44") (pin "L50") (pinfunction "50_L50") (pintype "bidirectional"))
    )
    (net (code "48") (name "/LVDS2_8_P") (class "Default")
      (node (ref "J41") (pin "23") (pinfunction "23_23") (pintype "bidirectional"))
      (node (ref "J44") (pin "L16") (pinfunction "16_L16") (pintype "bidirectional"))
    )
    (net (code "49") (name "/LVDS3_1_N") (class "Default")
      (node (ref "J42") (pin "3") (pinfunction "3_3") (pintype "bidirectional"))
      (node (ref "J44") (pin "L54") (pinfunction "54_L54") (pintype "bidirectional"))
    )
    (net (code "50") (name "/LVDS3_1_P") (class "Default")
      (node (ref "J42") (pin "2") (pinfunction "2_2") (pintype "bidirectional"))
      (node (ref "J44") (pin "L20") (pinfunction "20_L20") (pintype "bidirectional"))
    )
    (net (code "51") (name "/LVDS3_2_N") (class "Default")
      (node (ref "J42") (pin "6") (pinfunction "6_6") (pintype "bidirectional"))
      (node (ref "J44") (pin "L53") (pinfunction "53_L53") (pintype "bidirectional"))
    )
    (net (code "52") (name "/LVDS3_2_P") (class "Default")
      (node (ref "J42") (pin "5") (pinfunction "5_5") (pintype "bidirectional"))
      (node (ref "J44") (pin "L19") (pinfunction "19_L19") (pintype "bidirectional"))
    )
    (net (code "53") (name "/LVDS3_3_N") (class "Default")
      (node (ref "J42") (pin "9") (pinfunction "9_9") (pintype "bidirectional"))
      (node (ref "J44") (pin "L61") (pinfunction "61_L61") (pintype "bidirectional"))
    )
    (net (code "54") (name "/LVDS3_3_P") (class "Default")
      (node (ref "J42") (pin "8") (pinfunction "8_8") (pintype "bidirectional"))
      (node (ref "J44") (pin "L27") (pinfunction "27_L27") (pintype "bidirectional"))
    )
    (net (code "55") (name "/LVDS3_4_N") (class "Default")
      (node (ref "J42") (pin "12") (pinfunction "12_12") (pintype "bidirectional"))
      (node (ref "J44") (pin "L56") (pinfunction "56_L56") (pintype "bidirectional"))
    )
    (net (code "56") (name "/LVDS3_4_P") (class "Default")
      (node (ref "J42") (pin "11") (pinfunction "11_11") (pintype "bidirectional"))
      (node (ref "J44") (pin "L22") (pinfunction "22_L22") (pintype "bidirectional"))
    )
    (net (code "57") (name "/LVDS3_5_N") (class "Default")
      (node (ref "J42") (pin "15") (pinfunction "15_15") (pintype "bidirectional"))
      (node (ref "J44") (pin "L57") (pinfunction "57_L57") (pintype "bidirectional"))
    )
    (net (code "58") (name "/LVDS3_5_P") (class "Default")
      (node (ref "J42") (pin "14") (pinfunction "14_14") (pintype "bidirectional"))
      (node (ref "J44") (pin "L23") (pinfunction "23_L23") (pintype "bidirectional"))
    )
    (net (code "59") (name "/LVDS3_6_N") (class "Default")
      (node (ref "J42") (pin "18") (pinfunction "18_18") (pintype "bidirectional"))
      (node (ref "J44") (pin "L58") (pinfunction "58_L58") (pintype "bidirectional"))
    )
    (net (code "60") (name "/LVDS3_6_P") (class "Default")
      (node (ref "J42") (pin "17") (pinfunction "17_17") (pintype "bidirectional"))
      (node (ref "J44") (pin "L24") (pinfunction "24_L24") (pintype "bidirectional"))
    )
    (net (code "61") (name "/LVDS3_7_N") (class "Default")
      (node (ref "J42") (pin "21") (pinfunction "21_21") (pintype "bidirectional"))
      (node (ref "J44") (pin "L59") (pinfunction "59_L59") (pintype "bidirectional"))
    )
    (net (code "62") (name "/LVDS3_7_P") (class "Default")
      (node (ref "J42") (pin "20") (pinfunction "20_20") (pintype "bidirectional"))
      (node (ref "J44") (pin "L25") (pinfunction "25_L25") (pintype "bidirectional"))
    )
    (net (code "63") (name "/LVDS3_8_N") (class "Default")
      (node (ref "J42") (pin "24") (pinfunction "24_24") (pintype "bidirectional"))
      (node (ref "J44") (pin "L60") (pinfunction "60_L60") (pintype "bidirectional"))
    )
    (net (code "64") (name "/LVDS3_8_P") (class "Default")
      (node (ref "J42") (pin "23") (pinfunction "23_23") (pintype "bidirectional"))
      (node (ref "J44") (pin "L26") (pinfunction "26_L26") (pintype "bidirectional"))
    )
    (net (code "65") (name "/LVDS4_1_N") (class "Default")
      (node (ref "J43") (pin "3") (pinfunction "3_3") (pintype "bidirectional"))
      (node (ref "J44") (pin "L55") (pinfunction "55_L55") (pintype "bidirectional"))
    )
    (net (code "66") (name "/LVDS4_1_P") (class "Default")
      (node (ref "J43") (pin "2") (pinfunction "2_2") (pintype "bidirectional"))
      (node (ref "J44") (pin "L21") (pinfunction "21_L21") (pintype "bidirectional"))
    )
    (net (code "67") (name "/LVDS4_2_N") (class "Default")
      (node (ref "J43") (pin "6") (pinfunction "6_6") (pintype "bidirectional"))
      (node (ref "J44") (pin "L62") (pinfunction "62_L62") (pintype "bidirectional"))
    )
    (net (code "68") (name "/LVDS4_2_P") (class "Default")
      (node (ref "J43") (pin "5") (pinfunction "5_5") (pintype "bidirectional"))
      (node (ref "J44") (pin "L28") (pinfunction "28_L28") (pintype "bidirectional"))
    )
    (net (code "69") (name "/LVDS4_3_N") (class "Default")
      (node (ref "J43") (pin "9") (pinfunction "9_9") (pintype "bidirectional"))
      (node (ref "J44") (pin "L63") (pinfunction "63_L63") (pintype "bidirectional"))
    )
    (net (code "70") (name "/LVDS4_3_P") (class "Default")
      (node (ref "J43") (pin "8") (pinfunction "8_8") (pintype "bidirectional"))
      (node (ref "J44") (pin "L29") (pinfunction "29_L29") (pintype "bidirectional"))
    )
    (net (code "71") (name "/LVDS4_4_N") (class "Default")
      (node (ref "J43") (pin "12") (pinfunction "12_12") (pintype "bidirectional"))
      (node (ref "J44") (pin "L64") (pinfunction "64_L64") (pintype "bidirectional"))
    )
    (net (code "72") (name "/LVDS4_4_P") (class "Default")
      (node (ref "J43") (pin "11") (pinfunction "11_11") (pintype "bidirectional"))
      (node (ref "J44") (pin "L30") (pinfunction "30_L30") (pintype "bidirectional"))
    )
    (net (code "73") (name "/LVDS4_5_N") (class "Default")
      (node (ref "J43") (pin "15") (pinfunction "15_15") (pintype "bidirectional"))
      (node (ref "J44") (pin "L65") (pinfunction "65_L65") (pintype "bidirectional"))
    )
    (net (code "74") (name "/LVDS4_5_P") (class "Default")
      (node (ref "J43") (pin "14") (pinfunction "14_14") (pintype "bidirectional"))
      (node (ref "J44") (pin "L31") (pinfunction "31_L31") (pintype "bidirectional"))
    )
    (net (code "75") (name "/LVDS4_6_N") (class "Default")
      (node (ref "J43") (pin "18") (pinfunction "18_18") (pintype "bidirectional"))
      (node (ref "J44") (pin "L66") (pinfunction "66_L66") (pintype "bidirectional"))
    )
    (net (code "76") (name "/LVDS4_6_P") (class "Default")
      (node (ref "J43") (pin "17") (pinfunction "17_17") (pintype "bidirectional"))
      (node (ref "J44") (pin "L32") (pinfunction "32_L32") (pintype "bidirectional"))
    )
    (net (code "77") (name "/LVDS4_7_N") (class "Default")
      (node (ref "J43") (pin "21") (pinfunction "21_21") (pintype "bidirectional"))
      (node (ref "J44") (pin "L67") (pinfunction "67_L67") (pintype "bidirectional"))
    )
    (net (code "78") (name "/LVDS4_7_P") (class "Default")
      (node (ref "J43") (pin "20") (pinfunction "20_20") (pintype "bidirectional"))
      (node (ref "J44") (pin "L33") (pinfunction "33_L33") (pintype "bidirectional"))
    )
    (net (code "79") (name "/LVDS4_8_N") (class "Default")
      (node (ref "J43") (pin "24") (pinfunction "24_24") (pintype "bidirectional"))
      (node (ref "J44") (pin "L68") (pinfunction "68_L68") (pintype "bidirectional"))
    )
    (net (code "80") (name "/LVDS4_8_P") (class "Default")
      (node (ref "J43") (pin "23") (pinfunction "23_23") (pintype "bidirectional"))
      (node (ref "J44") (pin "L34") (pinfunction "34_L34") (pintype "bidirectional"))
    )
    (net (code "81") (name "/LVDS5_1_N") (class "Default")
      (node (ref "J44") (pin "U35") (pinfunction "35_U35") (pintype "bidirectional"))
      (node (ref "J45") (pin "3") (pinfunction "3_3") (pintype "bidirectional"))
    )
    (net (code "82") (name "/LVDS5_1_P") (class "Default")
      (node (ref "J44") (pin "U1") (pinfunction "1_U1") (pintype "bidirectional"))
      (node (ref "J45") (pin "2") (pinfunction "2_2") (pintype "bidirectional"))
    )
    (net (code "83") (name "/LVDS5_2_N") (class "Default")
      (node (ref "J44") (pin "U43") (pinfunction "43_U43") (pintype "bidirectional"))
      (node (ref "J45") (pin "6") (pinfunction "6_6") (pintype "bidirectional"))
    )
    (net (code "84") (name "/LVDS5_2_P") (class "Default")
      (node (ref "J44") (pin "U9") (pinfunction "9_U9") (pintype "bidirectional"))
      (node (ref "J45") (pin "5") (pinfunction "5_5") (pintype "bidirectional"))
    )
    (net (code "85") (name "/LVDS5_3_N") (class "Default")
      (node (ref "J44") (pin "U37") (pinfunction "37_U37") (pintype "bidirectional"))
      (node (ref "J45") (pin "9") (pinfunction "9_9") (pintype "bidirectional"))
    )
    (net (code "86") (name "/LVDS5_3_P") (class "Default")
      (node (ref "J44") (pin "U3") (pinfunction "3_U3") (pintype "bidirectional"))
      (node (ref "J45") (pin "8") (pinfunction "8_8") (pintype "bidirectional"))
    )
    (net (code "87") (name "/LVDS5_4_N") (class "Default")
      (node (ref "J44") (pin "U38") (pinfunction "38_U38") (pintype "bidirectional"))
      (node (ref "J45") (pin "12") (pinfunction "12_12") (pintype "bidirectional"))
    )
    (net (code "88") (name "/LVDS5_4_P") (class "Default")
      (node (ref "J44") (pin "U4") (pinfunction "4_U4") (pintype "bidirectional"))
      (node (ref "J45") (pin "11") (pinfunction "11_11") (pintype "bidirectional"))
    )
    (net (code "89") (name "/LVDS5_5_N") (class "Default")
      (node (ref "J44") (pin "U39") (pinfunction "39_U39") (pintype "bidirectional"))
      (node (ref "J45") (pin "15") (pinfunction "15_15") (pintype "bidirectional"))
    )
    (net (code "90") (name "/LVDS5_5_P") (class "Default")
      (node (ref "J44") (pin "U5") (pinfunction "5_U5") (pintype "bidirectional"))
      (node (ref "J45") (pin "14") (pinfunction "14_14") (pintype "bidirectional"))
    )
    (net (code "91") (name "/LVDS5_6_N") (class "Default")
      (node (ref "J44") (pin "U40") (pinfunction "40_U40") (pintype "bidirectional"))
      (node (ref "J45") (pin "18") (pinfunction "18_18") (pintype "bidirectional"))
    )
    (net (code "92") (name "/LVDS5_6_P") (class "Default")
      (node (ref "J44") (pin "U6") (pinfunction "6_U6") (pintype "bidirectional"))
      (node (ref "J45") (pin "17") (pinfunction "17_17") (pintype "bidirectional"))
    )
    (net (code "93") (name "/LVDS5_7_N") (class "Default")
      (node (ref "J44") (pin "U41") (pinfunction "41_U41") (pintype "bidirectional"))
      (node (ref "J45") (pin "21") (pinfunction "21_21") (pintype "bidirectional"))
    )
    (net (code "94") (name "/LVDS5_7_P") (class "Default")
      (node (ref "J44") (pin "U7") (pinfunction "7_U7") (pintype "bidirectional"))
      (node (ref "J45") (pin "20") (pinfunction "20_20") (pintype "bidirectional"))
    )
    (net (code "95") (name "/LVDS5_8_N") (class "Default")
      (node (ref "J44") (pin "U42") (pinfunction "42_U42") (pintype "bidirectional"))
      (node (ref "J45") (pin "24") (pinfunction "24_24") (pintype "bidirectional"))
    )
    (net (code "96") (name "/LVDS5_8_P") (class "Default")
      (node (ref "J44") (pin "U8") (pinfunction "8_U8") (pintype "bidirectional"))
      (node (ref "J45") (pin "23") (pinfunction "23_23") (pintype "bidirectional"))
    )
    (net (code "97") (name "/LVDS6_1_N") (class "Default")
      (node (ref "J44") (pin "U36") (pinfunction "36_U36") (pintype "bidirectional"))
      (node (ref "J46") (pin "3") (pinfunction "3_3") (pintype "bidirectional"))
    )
    (net (code "98") (name "/LVDS6_1_P") (class "Default")
      (node (ref "J44") (pin "U2") (pinfunction "2_U2") (pintype "bidirectional"))
      (node (ref "J46") (pin "2") (pinfunction "2_2") (pintype "bidirectional"))
    )
    (net (code "99") (name "/LVDS6_2_N") (class "Default")
      (node (ref "J44") (pin "U44") (pinfunction "44_U44") (pintype "bidirectional"))
      (node (ref "J46") (pin "6") (pinfunction "6_6") (pintype "bidirectional"))
    )
    (net (code "100") (name "/LVDS6_2_P") (class "Default")
      (node (ref "J44") (pin "U10") (pinfunction "10_U10") (pintype "bidirectional"))
      (node (ref "J46") (pin "5") (pinfunction "5_5") (pintype "bidirectional"))
    )
    (net (code "101") (name "/LVDS6_3_N") (class "Default")
      (node (ref "J44") (pin "U45") (pinfunction "45_U45") (pintype "bidirectional"))
      (node (ref "J46") (pin "9") (pinfunction "9_9") (pintype "bidirectional"))
    )
    (net (code "102") (name "/LVDS6_3_P") (class "Default")
      (node (ref "J44") (pin "U11") (pinfunction "11_U11") (pintype "bidirectional"))
      (node (ref "J46") (pin "8") (pinfunction "8_8") (pintype "bidirectional"))
    )
    (net (code "103") (name "/LVDS6_4_N") (class "Default")
      (node (ref "J44") (pin "U46") (pinfunction "46_U46") (pintype "bidirectional"))
      (node (ref "J46") (pin "12") (pinfunction "12_12") (pintype "bidirectional"))
    )
    (net (code "104") (name "/LVDS6_4_P") (class "Default")
      (node (ref "J44") (pin "U12") (pinfunction "12_U12") (pintype "bidirectional"))
      (node (ref "J46") (pin "11") (pinfunction "11_11") (pintype "bidirectional"))
    )
    (net (code "105") (name "/LVDS6_5_N") (class "Default")
      (node (ref "J44") (pin "U47") (pinfunction "47_U47") (pintype "bidirectional"))
      (node (ref "J46") (pin "15") (pinfunction "15_15") (pintype "bidirectional"))
    )
    (net (code "106") (name "/LVDS6_5_P") (class "Default")
      (node (ref "J44") (pin "U13") (pinfunction "13_U13") (pintype "bidirectional"))
      (node (ref "J46") (pin "14") (pinfunction "14_14") (pintype "bidirectional"))
    )
    (net (code "107") (name "/LVDS6_6_N") (class "Default")
      (node (ref "J44") (pin "U48") (pinfunction "48_U48") (pintype "bidirectional"))
      (node (ref "J46") (pin "18") (pinfunction "18_18") (pintype "bidirectional"))
    )
    (net (code "108") (name "/LVDS6_6_P") (class "Default")
      (node (ref "J44") (pin "U14") (pinfunction "14_U14") (pintype "bidirectional"))
      (node (ref "J46") (pin "17") (pinfunction "17_17") (pintype "bidirectional"))
    )
    (net (code "109") (name "/LVDS6_7_N") (class "Default")
      (node (ref "J44") (pin "U49") (pinfunction "49_U49") (pintype "bidirectional"))
      (node (ref "J46") (pin "21") (pinfunction "21_21") (pintype "bidirectional"))
    )
    (net (code "110") (name "/LVDS6_7_P") (class "Default")
      (node (ref "J44") (pin "U15") (pinfunction "15_U15") (pintype "bidirectional"))
      (node (ref "J46") (pin "20") (pinfunction "20_20") (pintype "bidirectional"))
    )
    (net (code "111") (name "/LVDS6_8_N") (class "Default")
      (node (ref "J44") (pin "U50") (pinfunction "50_U50") (pintype "bidirectional"))
      (node (ref "J46") (pin "24") (pinfunction "24_24") (pintype "bidirectional"))
    )
    (net (code "112") (name "/LVDS6_8_P") (class "Default")
      (node (ref "J44") (pin "U16") (pinfunction "16_U16") (pintype "bidirectional"))
      (node (ref "J46") (pin "23") (pinfunction "23_23") (pintype "bidirectional"))
    )
    (net (code "113") (name "/LVDS7_1_N") (class "Default")
      (node (ref "J44") (pin "U54") (pinfunction "54_U54") (pintype "bidirectional"))
      (node (ref "J47") (pin "3") (pinfunction "3_3") (pintype "bidirectional"))
    )
    (net (code "114") (name "/LVDS7_1_P") (class "Default")
      (node (ref "J44") (pin "U20") (pinfunction "20_U20") (pintype "bidirectional"))
      (node (ref "J47") (pin "2") (pinfunction "2_2") (pintype "bidirectional"))
    )
    (net (code "115") (name "/LVDS7_2_N") (class "Default")
      (node (ref "J44") (pin "U53") (pinfunction "53_U53") (pintype "bidirectional"))
      (node (ref "J47") (pin "6") (pinfunction "6_6") (pintype "bidirectional"))
    )
    (net (code "116") (name "/LVDS7_2_P") (class "Default")
      (node (ref "J44") (pin "U19") (pinfunction "19_U19") (pintype "bidirectional"))
      (node (ref "J47") (pin "5") (pinfunction "5_5") (pintype "bidirectional"))
    )
    (net (code "117") (name "/LVDS7_3_N") (class "Default")
      (node (ref "J44") (pin "U61") (pinfunction "61_U61") (pintype "bidirectional"))
      (node (ref "J47") (pin "9") (pinfunction "9_9") (pintype "bidirectional"))
    )
    (net (code "118") (name "/LVDS7_3_P") (class "Default")
      (node (ref "J44") (pin "U27") (pinfunction "27_U27") (pintype "bidirectional"))
      (node (ref "J47") (pin "8") (pinfunction "8_8") (pintype "bidirectional"))
    )
    (net (code "119") (name "/LVDS7_4_N") (class "Default")
      (node (ref "J44") (pin "U56") (pinfunction "56_U56") (pintype "bidirectional"))
      (node (ref "J47") (pin "12") (pinfunction "12_12") (pintype "bidirectional"))
    )
    (net (code "120") (name "/LVDS7_4_P") (class "Default")
      (node (ref "J44") (pin "U22") (pinfunction "22_U22") (pintype "bidirectional"))
      (node (ref "J47") (pin "11") (pinfunction "11_11") (pintype "bidirectional"))
    )
    (net (code "121") (name "/LVDS7_5_N") (class "Default")
      (node (ref "J44") (pin "U57") (pinfunction "57_U57") (pintype "bidirectional"))
      (node (ref "J47") (pin "15") (pinfunction "15_15") (pintype "bidirectional"))
    )
    (net (code "122") (name "/LVDS7_5_P") (class "Default")
      (node (ref "J44") (pin "U23") (pinfunction "23_U23") (pintype "bidirectional"))
      (node (ref "J47") (pin "14") (pinfunction "14_14") (pintype "bidirectional"))
    )
    (net (code "123") (name "/LVDS7_6_N") (class "Default")
      (node (ref "J44") (pin "U58") (pinfunction "58_U58") (pintype "bidirectional"))
      (node (ref "J47") (pin "18") (pinfunction "18_18") (pintype "bidirectional"))
    )
    (net (code "124") (name "/LVDS7_6_P") (class "Default")
      (node (ref "J44") (pin "U24") (pinfunction "24_U24") (pintype "bidirectional"))
      (node (ref "J47") (pin "17") (pinfunction "17_17") (pintype "bidirectional"))
    )
    (net (code "125") (name "/LVDS7_7_N") (class "Default")
      (node (ref "J44") (pin "U59") (pinfunction "59_U59") (pintype "bidirectional"))
      (node (ref "J47") (pin "21") (pinfunction "21_21") (pintype "bidirectional"))
    )
    (net (code "126") (name "/LVDS7_7_P") (class "Default")
      (node (ref "J44") (pin "U25") (pinfunction "25_U25") (pintype "bidirectional"))
      (node (ref "J47") (pin "20") (pinfunction "20_20") (pintype "bidirectional"))
    )
    (net (code "127") (name "/LVDS7_8_N") (class "Default")
      (node (ref "J44") (pin "U60") (pinfunction "60_U60") (pintype "bidirectional"))
      (node (ref "J47") (pin "24") (pinfunction "24_24") (pintype "bidirectional"))
    )
    (net (code "128") (name "/LVDS7_8_P") (class "Default")
      (node (ref "J44") (pin "U26") (pinfunction "26_U26") (pintype "bidirectional"))
      (node (ref "J47") (pin "23") (pinfunction "23_23") (pintype "bidirectional"))
    )
    (net (code "129") (name "/LVDS8_1_N") (class "Default")
      (node (ref "J44") (pin "U55") (pinfunction "55_U55") (pintype "bidirectional"))
      (node (ref "J48") (pin "3") (pinfunction "3_3") (pintype "bidirectional"))
    )
    (net (code "130") (name "/LVDS8_1_P") (class "Default")
      (node (ref "J44") (pin "U21") (pinfunction "21_U21") (pintype "bidirectional"))
      (node (ref "J48") (pin "2") (pinfunction "2_2") (pintype "bidirectional"))
    )
    (net (code "131") (name "/LVDS8_2_N") (class "Default")
      (node (ref "J44") (pin "U62") (pinfunction "62_U62") (pintype "bidirectional"))
      (node (ref "J48") (pin "6") (pinfunction "6_6") (pintype "bidirectional"))
    )
    (net (code "132") (name "/LVDS8_2_P") (class "Default")
      (node (ref "J44") (pin "U28") (pinfunction "28_U28") (pintype "bidirectional"))
      (node (ref "J48") (pin "5") (pinfunction "5_5") (pintype "bidirectional"))
    )
    (net (code "133") (name "/LVDS8_3_N") (class "Default")
      (node (ref "J44") (pin "U63") (pinfunction "63_U63") (pintype "bidirectional"))
      (node (ref "J48") (pin "9") (pinfunction "9_9") (pintype "bidirectional"))
    )
    (net (code "134") (name "/LVDS8_3_P") (class "Default")
      (node (ref "J44") (pin "U29") (pinfunction "29_U29") (pintype "bidirectional"))
      (node (ref "J48") (pin "8") (pinfunction "8_8") (pintype "bidirectional"))
    )
    (net (code "135") (name "/LVDS8_4_N") (class "Default")
      (node (ref "J44") (pin "U64") (pinfunction "64_U64") (pintype "bidirectional"))
      (node (ref "J48") (pin "12") (pinfunction "12_12") (pintype "bidirectional"))
    )
    (net (code "136") (name "/LVDS8_4_P") (class "Default")
      (node (ref "J44") (pin "U30") (pinfunction "30_U30") (pintype "bidirectional"))
      (node (ref "J48") (pin "11") (pinfunction "11_11") (pintype "bidirectional"))
    )
    (net (code "137") (name "/LVDS8_5_N") (class "Default")
      (node (ref "J44") (pin "U65") (pinfunction "65_U65") (pintype "bidirectional"))
      (node (ref "J48") (pin "15") (pinfunction "15_15") (pintype "bidirectional"))
    )
    (net (code "138") (name "/LVDS8_5_P") (class "Default")
      (node (ref "J44") (pin "U31") (pinfunction "31_U31") (pintype "bidirectional"))
      (node (ref "J48") (pin "14") (pinfunction "14_14") (pintype "bidirectional"))
    )
    (net (code "139") (name "/LVDS8_6_N") (class "Default")
      (node (ref "J44") (pin "U66") (pinfunction "66_U66") (pintype "bidirectional"))
      (node (ref "J48") (pin "18") (pinfunction "18_18") (pintype "bidirectional"))
    )
    (net (code "140") (name "/LVDS8_6_P") (class "Default")
      (node (ref "J44") (pin "U32") (pinfunction "32_U32") (pintype "bidirectional"))
      (node (ref "J48") (pin "17") (pinfunction "17_17") (pintype "bidirectional"))
    )
    (net (code "141") (name "/LVDS8_7_N") (class "Default")
      (node (ref "J44") (pin "U67") (pinfunction "67_U67") (pintype "bidirectional"))
      (node (ref "J48") (pin "21") (pinfunction "21_21") (pintype "bidirectional"))
    )
    (net (code "142") (name "/LVDS8_7_P") (class "Default")
      (node (ref "J44") (pin "U33") (pinfunction "33_U33") (pintype "bidirectional"))
      (node (ref "J48") (pin "20") (pinfunction "20_20") (pintype "bidirectional"))
    )
    (net (code "143") (name "/LVDS8_8_N") (class "Default")
      (node (ref "J44") (pin "U68") (pinfunction "68_U68") (pintype "bidirectional"))
      (node (ref "J48") (pin "24") (pinfunction "24_24") (pintype "bidirectional"))
    )
    (net (code "144") (name "/LVDS8_8_P") (class "Default")
      (node (ref "J44") (pin "U34") (pinfunction "34_U34") (pintype "bidirectional"))
      (node (ref "J48") (pin "23") (pinfunction "23_23") (pintype "bidirectional"))
    )
    (net (code "145") (name "/VHDCI1_SCL") (class "Default")
      (node (ref "IC33") (pin "19") (pinfunction "SCL_19") (pintype "bidirectional"))
      (node (ref "J44") (pin "L17") (pinfunction "17_L17") (pintype "bidirectional"))
    )
    (net (code "146") (name "/VHDCI1_SDA") (class "Default")
      (node (ref "IC33") (pin "20") (pinfunction "SDA_20") (pintype "bidirectional"))
      (node (ref "J44") (pin "L51") (pinfunction "51_L51") (pintype "bidirectional"))
    )
    (net (code "147") (name "/VHDCI2_SCL") (class "Default")
      (node (ref "IC35") (pin "19") (pinfunction "SCL_19") (pintype "bidirectional"))
      (node (ref "J44") (pin "U17") (pinfunction "17_U17") (pintype "bidirectional"))
    )
    (net (code "148") (name "/VHDCI2_SDA") (class "Default")
      (node (ref "IC35") (pin "20") (pinfunction "SDA_20") (pintype "bidirectional"))
      (node (ref "J44") (pin "U51") (pinfunction "51_U51") (pintype "bidirectional"))
    )
    (net (code "149") (name "GND") (class "Default")
      (node (ref "B5") (pin "1") (pinfunction "1_1") (pintype "bidirectional"))
      (node (ref "B6") (pin "1") (pinfunction "1_1") (pintype "bidirectional"))
      (node (ref "B8") (pin "1") (pinfunction "1_1") (pintype "bidirectional"))
      (node (ref "C76") (pin "1") (pinfunction "1_1") (pintype "passive"))
      (node (ref "C77") (pin "1") (pinfunction "1_1") (pintype "passive"))
      (node (ref "C78") (pin "1") (pinfunction "1_1") (pintype "passive"))
      (node (ref "C79") (pin "1") (pinfunction "1_1") (pintype "passive"))
      (node (ref "C80") (pin "1") (pinfunction "1_1") (pintype "passive"))
      (node (ref "C81") (pin "2") (pinfunction "2_2") (pintype "passive"))
      (node (ref "C82") (pin "1") (pinfunction "1_1") (pintype "passive"))
      (node (ref "C83") (pin "1") (pinfunction "1_1") (pintype "passive"))
      (node (ref "C84") (pin "1") (pinfunction "1_1") (pintype "passive"))
      (node (ref "C85") (pin "1") (pinfunction "1_1") (pintype "passive"))
      (node (ref "C86") (pin "1") (pinfunction "1_1") (pintype "passive"))
      (node (ref "C87") (pin "2") (pinfunction "2_2") (pintype "passive"))
      (node (ref "C88") (pin "2") (pinfunction "2_2") (pintype "passive"))
      (node (ref "FL1") (pin "4") (pinfunction "CG_4") (pintype "passive"))
      (node (ref "IC33") (pin "25") (pinfunction "EP_25") (pintype "power_in"))
      (node (ref "IC33") (pin "9") (pinfunction "GND_9") (pintype "power_in"))
      (node (ref "IC34") (pin "2") (pinfunction "VSS_2") (pintype "power_in"))
      (node (ref "IC35") (pin "25") (pinfunction "EP_25") (pintype "power_in"))
      (node (ref "IC35") (pin "9") (pinfunction "GND_9") (pintype "power_in"))
      (node (ref "IC36") (pin "2") (pinfunction "VSS_2") (pintype "power_in"))
      (node (ref "J40") (pin "1") (pinfunction "1_1") (pintype "bidirectional"))
      (node (ref "J40") (pin "10") (pinfunction "10_10") (pintype "bidirectional"))
      (node (ref "J40") (pin "13") (pinfunction "13_13") (pintype "bidirectional"))
      (node (ref "J40") (pin "16") (pinfunction "16_16") (pintype "bidirectional"))
      (node (ref "J40") (pin "19") (pinfunction "19_19") (pintype "bidirectional"))
      (node (ref "J40") (pin "22") (pinfunction "22_22") (pintype "bidirectional"))
      (node (ref "J40") (pin "25") (pinfunction "25_25") (pintype "bidirectional"))
      (node (ref "J40") (pin "4") (pinfunction "4_4") (pintype "bidirectional"))
      (node (ref "J40") (pin "7") (pinfunction "7_7") (pintype "bidirectional"))
      (node (ref "J41") (pin "1") (pinfunction "1_1") (pintype "bidirectional"))
      (node (ref "J41") (pin "10") (pinfunction "10_10") (pintype "bidirectional"))
      (node (ref "J41") (pin "13") (pinfunction "13_13") (pintype "bidirectional"))
      (node (ref "J41") (pin "16") (pinfunction "16_16") (pintype "bidirectional"))
      (node (ref "J41") (pin "19") (pinfunction "19_19") (pintype "bidirectional"))
      (node (ref "J41") (pin "22") (pinfunction "22_22") (pintype "bidirectional"))
      (node (ref "J41") (pin "25") (pinfunction "25_25") (pintype "bidirectional"))
      (node (ref "J41") (pin "4") (pinfunction "4_4") (pintype "bidirectional"))
      (node (ref "J41") (pin "7") (pinfunction "7_7") (pintype "bidirectional"))
      (node (ref "J42") (pin "1") (pinfunction "1_1") (pintype "bidirectional"))
      (node (ref "J42") (pin "10") (pinfunction "10_10") (pintype "bidirectional"))
      (node (ref "J42") (pin "13") (pinfunction "13_13") (pintype "bidirectional"))
      (node (ref "J42") (pin "16") (pinfunction "16_16") (pintype "bidirectional"))
      (node (ref "J42") (pin "19") (pinfunction "19_19") (pintype "bidirectional"))
      (node (ref "J42") (pin "22") (pinfunction "22_22") (pintype "bidirectional"))
      (node (ref "J42") (pin "25") (pinfunction "25_25") (pintype "bidirectional"))
      (node (ref "J42") (pin "4") (pinfunction "4_4") (pintype "bidirectional"))
      (node (ref "J42") (pin "7") (pinfunction "7_7") (pintype "bidirectional"))
      (node (ref "J43") (pin "1") (pinfunction "1_1") (pintype "bidirectional"))
      (node (ref "J43") (pin "10") (pinfunction "10_10") (pintype "bidirectional"))
      (node (ref "J43") (pin "13") (pinfunction "13_13") (pintype "bidirectional"))
      (node (ref "J43") (pin "16") (pinfunction "16_16") (pintype "bidirectional"))
      (node (ref "J43") (pin "19") (pinfunction "19_19") (pintype "bidirectional"))
      (node (ref "J43") (pin "22") (pinfunction "22_22") (pintype "bidirectional"))
      (node (ref "J43") (pin "25") (pinfunction "25_25") (pintype "bidirectional"))
      (node (ref "J43") (pin "4") (pinfunction "4_4") (pintype "bidirectional"))
      (node (ref "J43") (pin "7") (pinfunction "7_7") (pintype "bidirectional"))
      (node (ref "J44") (pin "69") (pinfunction "69_69") (pintype "passive"))
      (node (ref "J44") (pin "70") (pinfunction "70_70") (pintype "passive"))
      (node (ref "J44") (pin "71") (pinfunction "71_71") (pintype "passive"))
      (node (ref "J44") (pin "72") (pinfunction "72_72") (pintype "passive"))
      (node (ref "J44") (pin "L18") (pinfunction "18_L18") (pintype "bidirectional"))
      (node (ref "J44") (pin "U18") (pinfunction "18_U18") (pintype "bidirectional"))
      (node (ref "J45") (pin "1") (pinfunction "1_1") (pintype "bidirectional"))
      (node (ref "J45") (pin "10") (pinfunction "10_10") (pintype "bidirectional"))
      (node (ref "J45") (pin "13") (pinfunction "13_13") (pintype "bidirectional"))
      (node (ref "J45") (pin "16") (pinfunction "16_16") (pintype "bidirectional"))
      (node (ref "J45") (pin "19") (pinfunction "19_19") (pintype "bidirectional"))
      (node (ref "J45") (pin "22") (pinfunction "22_22") (pintype "bidirectional"))
      (node (ref "J45") (pin "25") (pinfunction "25_25") (pintype "bidirectional"))
      (node (ref "J45") (pin "4") (pinfunction "4_4") (pintype "bidirectional"))
      (node (ref "J45") (pin "7") (pinfunction "7_7") (pintype "bidirectional"))
      (node (ref "J46") (pin "1") (pinfunction "1_1") (pintype "bidirectional"))
      (node (ref "J46") (pin "10") (pinfunction "10_10") (pintype "bidirectional"))
      (node (ref "J46") (pin "13") (pinfunction "13_13") (pintype "bidirectional"))
      (node (ref "J46") (pin "16") (pinfunction "16_16") (pintype "bidirectional"))
      (node (ref "J46") (pin "19") (pinfunction "19_19") (pintype "bidirectional"))
      (node (ref "J46") (pin "22") (pinfunction "22_22") (pintype "bidirectional"))
      (node (ref "J46") (pin "25") (pinfunction "25_25") (pintype "bidirectional"))
      (node (ref "J46") (pin "4") (pinfunction "4_4") (pintype "bidirectional"))
      (node (ref "J46") (pin "7") (pinfunction "7_7") (pintype "bidirectional"))
      (node (ref "J47") (pin "1") (pinfunction "1_1") (pintype "bidirectional"))
      (node (ref "J47") (pin "10") (pinfunction "10_10") (pintype "bidirectional"))
      (node (ref "J47") (pin "13") (pinfunction "13_13") (pintype "bidirectional"))
      (node (ref "J47") (pin "16") (pinfunction "16_16") (pintype "bidirectional"))
      (node (ref "J47") (pin "19") (pinfunction "19_19") (pintype "bidirectional"))
      (node (ref "J47") (pin "22") (pinfunction "22_22") (pintype "bidirectional"))
      (node (ref "J47") (pin "25") (pinfunction "25_25") (pintype "bidirectional"))
      (node (ref "J47") (pin "4") (pinfunction "4_4") (pintype "bidirectional"))
      (node (ref "J47") (pin "7") (pinfunction "7_7") (pintype "bidirectional"))
      (node (ref "J48") (pin "1") (pinfunction "1_1") (pintype "bidirectional"))
      (node (ref "J48") (pin "10") (pinfunction "10_10") (pintype "bidirectional"))
      (node (ref "J48") (pin "13") (pinfunction "13_13") (pintype "bidirectional"))
      (node (ref "J48") (pin "16") (pinfunction "16_16") (pintype "bidirectional"))
      (node (ref "J48") (pin "19") (pinfunction "19_19") (pintype "bidirectional"))
      (node (ref "J48") (pin "22") (pinfunction "22_22") (pintype "bidirectional"))
      (node (ref "J48") (pin "25") (pinfunction "25_25") (pintype "bidirectional"))
      (node (ref "J48") (pin "4") (pinfunction "4_4") (pintype "bidirectional"))
      (node (ref "J48") (pin "7") (pinfunction "7_7") (pintype "bidirectional"))
      (node (ref "J49") (pin "a11") (pinfunction "a11_a11") (pintype "bidirectional"))
      (node (ref "J49") (pin "a17") (pinfunction "a17_a17") (pintype "bidirectional"))
      (node (ref "J49") (pin "a19") (pinfunction "a19_a19") (pintype "bidirectional"))
      (node (ref "J49") (pin "a9") (pinfunction "a9_a9") (pintype "bidirectional"))
      (node (ref "J49") (pin "b12") (pinfunction "b12_b12") (pintype "bidirectional"))
      (node (ref "J49") (pin "b20") (pinfunction "b20_b20") (pintype "bidirectional"))
      (node (ref "J49") (pin "b22") (pinfunction "b22_b22") (pintype "bidirectional"))
      (node (ref "J49") (pin "b23") (pinfunction "b23_b23") (pintype "bidirectional"))
      (node (ref "J49") (pin "c9") (pinfunction "c9_c9") (pintype "bidirectional"))
      (node (ref "LD1") (pin "1") (pinfunction "C_1") (pintype "passive"))
      (node (ref "LD2") (pin "1") (pinfunction "C_1") (pintype "passive"))
      (node (ref "LD3") (pin "1") (pinfunction "C_1") (pintype "passive"))
      (node (ref "R178") (pin "1") (pinfunction "1_1") (pintype "passive"))
      (node (ref "R179") (pin "1") (pinfunction "1_1") (pintype "passive"))
      (node (ref "R181") (pin "1") (pinfunction "1_1") (pintype "passive"))
      (node (ref "R192") (pin "1") (pinfunction "1_1") (pintype "passive"))
      (node (ref "R193") (pin "1") (pinfunction "1_1") (pintype "passive"))
      (node (ref "R195") (pin "1") (pinfunction "1_1") (pintype "passive"))
    )
    (net (code "150") (name "INPUT_GND") (class "Default")
      (node (ref "FL1") (pin "3") (pinfunction "PSG_3") (pintype "passive"))
      (node (ref "J1") (pin "1") (pinfunction "1_1") (pintype "bidirectional"))
      (node (ref "J2") (pin "1") (pinfunction "1_1") (pintype "bidirectional"))
      (node (ref "J49") (pin "b2") (pinfunction "b2_b2") (pintype "bidirectional"))
    )
    (net (code "151") (name "Net-(FL1-B)") (class "Default")
      (node (ref "FL1") (pin "1") (pinfunction "B_1") (pintype "passive"))
      (node (ref "J1") (pin "3") (pinfunction "3_3") (pintype "bidirectional"))
      (node (ref "J2") (pin "3") (pinfunction "3_3") (pintype "bidirectional"))
    )
    (net (code "152") (name "Net-(IC33-A0)") (class "Default")
      (node (ref "IC33") (pin "22") (pinfunction "A0_22") (pintype "input"))
      (node (ref "R181") (pin "2") (pinfunction "2_2") (pintype "passive"))
    )
    (net (code "153") (name "Net-(IC33-A1)") (class "Default")
      (node (ref "IC33") (pin "23") (pinfunction "A1_23") (pintype "input"))
      (node (ref "R179") (pin "2") (pinfunction "2_2") (pintype "passive"))
    )
    (net (code "154") (name "Net-(IC33-A2)") (class "Default")
      (node (ref "IC33") (pin "18") (pinfunction "A2_18") (pintype "input"))
      (node (ref "R178") (pin "2") (pinfunction "2_2") (pintype "passive"))
    )
    (net (code "155") (name "Net-(IC33-SC0)") (class "Default")
      (node (ref "B2") (pin "1") (pinfunction "1_1") (pintype "bidirectional"))
      (node (ref "IC33") (pin "2") (pinfunction "SC0_2") (pintype "bidirectional"))
      (node (ref "IC34") (pin "1") (pinfunction "SCL_1") (pintype "input"))
      (node (ref "R174") (pin "1") (pinfunction "1_1") (pintype "passive"))
    )
    (net (code "156") (name "Net-(IC33-SD0)") (class "Default")
      (node (ref "B1") (pin "1") (pinfunction "1_1") (pintype "bidirectional"))
      (node (ref "IC33") (pin "1") (pinfunction "SD0_1") (pintype "bidirectional"))
      (node (ref "IC34") (pin "3") (pinfunction "SDA_3") (pintype "bidirectional"))
      (node (ref "R175") (pin "1") (pinfunction "1_1") (pintype "passive"))
    )
    (net (code "157") (name "Net-(IC35-A0)") (class "Default")
      (node (ref "IC35") (pin "22") (pinfunction "A0_22") (pintype "input"))
      (node (ref "R195") (pin "2") (pinfunction "2_2") (pintype "passive"))
    )
    (net (code "158") (name "Net-(IC35-A1)") (class "Default")
      (node (ref "IC35") (pin "23") (pinfunction "A1_23") (pintype "input"))
      (node (ref "R193") (pin "2") (pinfunction "2_2") (pintype "passive"))
    )
    (net (code "159") (name "Net-(IC35-A2)") (class "Default")
      (node (ref "IC35") (pin "18") (pinfunction "A2_18") (pintype "input"))
      (node (ref "R192") (pin "2") (pinfunction "2_2") (pintype "passive"))
    )
    (net (code "160") (name "Net-(IC35-SC0)") (class "Default")
      (node (ref "B4") (pin "1") (pinfunction "1_1") (pintype "bidirectional"))
      (node (ref "IC35") (pin "2") (pinfunction "SC0_2") (pintype "bidirectional"))
      (node (ref "IC36") (pin "1") (pinfunction "SCL_1") (pintype "input"))
      (node (ref "R188") (pin "1") (pinfunction "1_1") (pintype "passive"))
    )
    (net (code "161") (name "Net-(IC35-SD0)") (class "Default")
      (node (ref "B3") (pin "1") (pinfunction "1_1") (pintype "bidirectional"))
      (node (ref "IC35") (pin "1") (pinfunction "SD0_1") (pintype "bidirectional"))
      (node (ref "IC36") (pin "3") (pinfunction "SDA_3") (pintype "bidirectional"))
      (node (ref "R189") (pin "1") (pinfunction "1_1") (pintype "passive"))
    )
    (net (code "162") (name "Net-(LD1-A)") (class "Default")
      (node (ref "LD1") (pin "2") (pinfunction "A_2") (pintype "passive"))
      (node (ref "R1") (pin "1") (pinfunction "1_1") (pintype "passive"))
    )
    (net (code "163") (name "Net-(LD2-A)") (class "Default")
      (node (ref "LD2") (pin "2") (pinfunction "A_2") (pintype "passive"))
      (node (ref "R2") (pin "2") (pinfunction "2_2") (pintype "passive"))
    )
    (net (code "164") (name "Net-(LD3-A)") (class "Default")
      (node (ref "LD3") (pin "2") (pinfunction "A_2") (pintype "passive"))
      (node (ref "R3") (pin "2") (pinfunction "2_2") (pintype "passive"))
    )
    (net (code "165") (name "P3V3_MP1") (class "Default")
      (node (ref "B7") (pin "1") (pinfunction "1_1") (pintype "bidirectional"))
      (node (ref "C76") (pin "2") (pinfunction "2_2") (pintype "passive"))
      (node (ref "C77") (pin "2") (pinfunction "2_2") (pintype "passive"))
      (node (ref "C78") (pin "2") (pinfunction "2_2") (pintype "passive"))
      (node (ref "C79") (pin "2") (pinfunction "2_2") (pintype "passive"))
      (node (ref "C80") (pin "2") (pinfunction "2_2") (pintype "passive"))
      (node (ref "C81") (pin "1") (pinfunction "1_1") (pintype "passive"))
      (node (ref "IC33") (pin "21") (pinfunction "VCC_21") (pintype "power_in"))
      (node (ref "IC33") (pin "24") (pinfunction "~{RESET}_24") (pintype "input"))
      (node (ref "IC34") (pin "4") (pinfunction "VCC_4") (pintype "power_in"))
      (node (ref "J40") (pin "30") (pinfunction "30_30") (pintype "bidirectional"))
      (node (ref "J41") (pin "30") (pinfunction "30_30") (pintype "bidirectional"))
      (node (ref "J42") (pin "30") (pinfunction "30_30") (pintype "bidirectional"))
      (node (ref "J43") (pin "30") (pinfunction "30_30") (pintype "bidirectional"))
      (node (ref "J44") (pin "L52") (pinfunction "52_L52") (pintype "bidirectional"))
      (node (ref "R174") (pin "2") (pinfunction "2_2") (pintype "passive"))
      (node (ref "R175") (pin "2") (pinfunction "2_2") (pintype "passive"))
      (node (ref "R176") (pin "2") (pinfunction "2_2") (pintype "passive"))
      (node (ref "R177") (pin "2") (pinfunction "2_2") (pintype "passive"))
      (node (ref "R180") (pin "2") (pinfunction "2_2") (pintype "passive"))
      (node (ref "R182") (pin "2") (pinfunction "2_2") (pintype "passive"))
      (node (ref "R183") (pin "2") (pinfunction "2_2") (pintype "passive"))
      (node (ref "R184") (pin "2") (pinfunction "2_2") (pintype "passive"))
      (node (ref "R185") (pin "2") (pinfunction "2_2") (pintype "passive"))
      (node (ref "R186") (pin "2") (pinfunction "2_2") (pintype "passive"))
      (node (ref "R2") (pin "1") (pinfunction "1_1") (pintype "passive"))
    )
    (net (code "166") (name "P3V3_MP2") (class "Default")
      (node (ref "B9") (pin "1") (pinfunction "1_1") (pintype "bidirectional"))
      (node (ref "C82") (pin "2") (pinfunction "2_2") (pintype "passive"))
      (node (ref "C83") (pin "2") (pinfunction "2_2") (pintype "passive"))
      (node (ref "C84") (pin "2") (pinfunction "2_2") (pintype "passive"))
      (node (ref "C85") (pin "2") (pinfunction "2_2") (pintype "passive"))
      (node (ref "C86") (pin "2") (pinfunction "2_2") (pintype "passive"))
      (node (ref "C87") (pin "1") (pinfunction "1_1") (pintype "passive"))
      (node (ref "IC35") (pin "21") (pinfunction "VCC_21") (pintype "power_in"))
      (node (ref "IC35") (pin "24") (pinfunction "~{RESET}_24") (pintype "input"))
      (node (ref "IC36") (pin "4") (pinfunction "VCC_4") (pintype "power_in"))
      (node (ref "J44") (pin "U52") (pinfunction "52_U52") (pintype "bidirectional"))
      (node (ref "J45") (pin "30") (pinfunction "30_30") (pintype "bidirectional"))
      (node (ref "J46") (pin "30") (pinfunction "30_30") (pintype "bidirectional"))
      (node (ref "J47") (pin "30") (pinfunction "30_30") (pintype "bidirectional"))
      (node (ref "J48") (pin "30") (pinfunction "30_30") (pintype "bidirectional"))
      (node (ref "R188") (pin "2") (pinfunction "2_2") (pintype "passive"))
      (node (ref "R189") (pin "2") (pinfunction "2_2") (pintype "passive"))
      (node (ref "R190") (pin "2") (pinfunction "2_2") (pintype "passive"))
      (node (ref "R191") (pin "2") (pinfunction "2_2") (pintype "passive"))
      (node (ref "R194") (pin "2") (pinfunction "2_2") (pintype "passive"))
      (node (ref "R196") (pin "2") (pinfunction "2_2") (pintype "passive"))
      (node (ref "R197") (pin "2") (pinfunction "2_2") (pintype "passive"))
      (node (ref "R198") (pin "2") (pinfunction "2_2") (pintype "passive"))
      (node (ref "R199") (pin "2") (pinfunction "2_2") (pintype "passive"))
      (node (ref "R200") (pin "2") (pinfunction "2_2") (pintype "passive"))
      (node (ref "R3") (pin "1") (pinfunction "1_1") (pintype "passive"))
    )
    (net (code "167") (name "P5V0") (class "Default")
      (node (ref "J49") (pin "a32") (pinfunction "a32_a32") (pintype "bidirectional"))
      (node (ref "J49") (pin "b32") (pinfunction "b32_b32") (pintype "bidirectional"))
      (node (ref "J49") (pin "c32") (pinfunction "c32_c32") (pintype "bidirectional"))
    )
    (net (code "168") (name "P12V0") (class "Default")
      (node (ref "B10") (pin "1") (pinfunction "1_1") (pintype "bidirectional"))
      (node (ref "C88") (pin "1") (pinfunction "1_1") (pintype "passive"))
      (node (ref "FL1") (pin "2") (pinfunction "CB_2") (pintype "passive"))
      (node (ref "J40") (pin "28") (pinfunction "28_28") (pintype "bidirectional"))
      (node (ref "J40") (pin "29") (pinfunction "29_29") (pintype "bidirectional"))
      (node (ref "J41") (pin "28") (pinfunction "28_28") (pintype "bidirectional"))
      (node (ref "J41") (pin "29") (pinfunction "29_29") (pintype "bidirectional"))
      (node (ref "J42") (pin "28") (pinfunction "28_28") (pintype "bidirectional"))
      (node (ref "J42") (pin "29") (pinfunction "29_29") (pintype "bidirectional"))
      (node (ref "J43") (pin "28") (pinfunction "28_28") (pintype "bidirectional"))
      (node (ref "J43") (pin "29") (pinfunction "29_29") (pintype "bidirectional"))
      (node (ref "J45") (pin "28") (pinfunction "28_28") (pintype "bidirectional"))
      (node (ref "J45") (pin "29") (pinfunction "29_29") (pintype "bidirectional"))
      (node (ref "J46") (pin "28") (pinfunction "28_28") (pintype "bidirectional"))
      (node (ref "J46") (pin "29") (pinfunction "29_29") (pintype "bidirectional"))
      (node (ref "J47") (pin "28") (pinfunction "28_28") (pintype "bidirectional"))
      (node (ref "J47") (pin "29") (pinfunction "29_29") (pintype "bidirectional"))
      (node (ref "J48") (pin "28") (pinfunction "28_28") (pintype "bidirectional"))
      (node (ref "J48") (pin "29") (pinfunction "29_29") (pintype "bidirectional"))
      (node (ref "J49") (pin "b31") (pinfunction "b31_b31") (pintype "bidirectional"))
      (node (ref "J49") (pin "c31") (pinfunction "c31_c31") (pintype "bidirectional"))
      (node (ref "R1") (pin "2") (pinfunction "2_2") (pintype "passive"))
    )
    (net (code "169") (name "unconnected-(IC33-SC5-Pad13)") (class "Default")
      (node (ref "IC33") (pin "13") (pinfunction "SC5_13") (pintype "bidirectional"))
    )
    (net (code "170") (name "unconnected-(IC33-SC6-Pad15)") (class "Default")
      (node (ref "IC33") (pin "15") (pinfunction "SC6_15") (pintype "bidirectional"))
    )
    (net (code "171") (name "unconnected-(IC33-SC7-Pad17)") (class "Default")
      (node (ref "IC33") (pin "17") (pinfunction "SC7_17") (pintype "bidirectional"))
    )
    (net (code "172") (name "unconnected-(IC33-SD5-Pad12)") (class "Default")
      (node (ref "IC33") (pin "12") (pinfunction "SD5_12") (pintype "bidirectional"))
    )
    (net (code "173") (name "unconnected-(IC33-SD6-Pad14)") (class "Default")
      (node (ref "IC33") (pin "14") (pinfunction "SD6_14") (pintype "bidirectional"))
    )
    (net (code "174") (name "unconnected-(IC33-SD7-Pad16)") (class "Default")
      (node (ref "IC33") (pin "16") (pinfunction "SD7_16") (pintype "bidirectional"))
    )
    (net (code "175") (name "unconnected-(IC34-NC-Pad5)") (class "Default")
      (node (ref "IC34") (pin "5") (pinfunction "NC_5") (pintype "passive"))
    )
    (net (code "176") (name "unconnected-(IC35-SC5-Pad13)") (class "Default")
      (node (ref "IC35") (pin "13") (pinfunction "SC5_13") (pintype "bidirectional"))
    )
    (net (code "177") (name "unconnected-(IC35-SC6-Pad15)") (class "Default")
      (node (ref "IC35") (pin "15") (pinfunction "SC6_15") (pintype "bidirectional"))
    )
    (net (code "178") (name "unconnected-(IC35-SC7-Pad17)") (class "Default")
      (node (ref "IC35") (pin "17") (pinfunction "SC7_17") (pintype "bidirectional"))
    )
    (net (code "179") (name "unconnected-(IC35-SD5-Pad12)") (class "Default")
      (node (ref "IC35") (pin "12") (pinfunction "SD5_12") (pintype "bidirectional"))
    )
    (net (code "180") (name "unconnected-(IC35-SD6-Pad14)") (class "Default")
      (node (ref "IC35") (pin "14") (pinfunction "SD6_14") (pintype "bidirectional"))
    )
    (net (code "181") (name "unconnected-(IC35-SD7-Pad16)") (class "Default")
      (node (ref "IC35") (pin "16") (pinfunction "SD7_16") (pintype "bidirectional"))
    )
    (net (code "182") (name "unconnected-(IC36-NC-Pad5)") (class "Default")
      (node (ref "IC36") (pin "5") (pinfunction "NC_5") (pintype "passive"))
    )
    (net (code "183") (name "unconnected-(J1-Pad2)") (class "Default")
      (node (ref "J1") (pin "2") (pinfunction "2_2") (pintype "bidirectional"))
    )
    (net (code "184") (name "unconnected-(J2-Pad2)") (class "Default")
      (node (ref "J2") (pin "2") (pinfunction "2_2") (pintype "bidirectional"))
    )
    (net (code "185") (name "unconnected-(J49-Pada1)") (class "Default")
      (node (ref "J49") (pin "a1") (pinfunction "a1_a1") (pintype "bidirectional"))
    )
    (net (code "186") (name "unconnected-(J49-Pada2)") (class "Default")
      (node (ref "J49") (pin "a2") (pinfunction "a2_a2") (pintype "bidirectional"))
    )
    (net (code "187") (name "unconnected-(J49-Pada3)") (class "Default")
      (node (ref "J49") (pin "a3") (pinfunction "a3_a3") (pintype "bidirectional"))
    )
    (net (code "188") (name "unconnected-(J49-Pada4)") (class "Default")
      (node (ref "J49") (pin "a4") (pinfunction "a4_a4") (pintype "bidirectional"))
    )
    (net (code "189") (name "unconnected-(J49-Pada5)") (class "Default")
      (node (ref "J49") (pin "a5") (pinfunction "a5_a5") (pintype "bidirectional"))
    )
    (net (code "190") (name "unconnected-(J49-Pada6)") (class "Default")
      (node (ref "J49") (pin "a6") (pinfunction "a6_a6") (pintype "bidirectional"))
    )
    (net (code "191") (name "unconnected-(J49-Pada7)") (class "Default")
      (node (ref "J49") (pin "a7") (pinfunction "a7_a7") (pintype "bidirectional"))
    )
    (net (code "192") (name "unconnected-(J49-Pada8)") (class "Default")
      (node (ref "J49") (pin "a8") (pinfunction "a8_a8") (pintype "bidirectional"))
    )
    (net (code "193") (name "unconnected-(J49-Pada10)") (class "Default")
      (node (ref "J49") (pin "a10") (pinfunction "a10_a10") (pintype "bidirectional"))
    )
    (net (code "194") (name "unconnected-(J49-Pada12)") (class "Default")
      (node (ref "J49") (pin "a12") (pinfunction "a12_a12") (pintype "bidirectional"))
    )
    (net (code "195") (name "unconnected-(J49-Pada13)") (class "Default")
      (node (ref "J49") (pin "a13") (pinfunction "a13_a13") (pintype "bidirectional"))
    )
    (net (code "196") (name "unconnected-(J49-Pada14)") (class "Default")
      (node (ref "J49") (pin "a14") (pinfunction "a14_a14") (pintype "bidirectional"))
    )
    (net (code "197") (name "unconnected-(J49-Pada15)") (class "Default")
      (node (ref "J49") (pin "a15") (pinfunction "a15_a15") (pintype "bidirectional"))
    )
    (net (code "198") (name "unconnected-(J49-Pada16)") (class "Default")
      (node (ref "J49") (pin "a16") (pinfunction "a16_a16") (pintype "bidirectional"))
    )
    (net (code "199") (name "unconnected-(J49-Pada18)") (class "Default")
      (node (ref "J49") (pin "a18") (pinfunction "a18_a18") (pintype "bidirectional"))
    )
    (net (code "200") (name "unconnected-(J49-Pada20)") (class "Default")
      (node (ref "J49") (pin "a20") (pinfunction "a20_a20") (pintype "bidirectional"))
    )
    (net (code "201") (name "unconnected-(J49-Pada21)") (class "Default")
      (node (ref "J49") (pin "a21") (pinfunction "a21_a21") (pintype "bidirectional"))
    )
    (net (code "202") (name "unconnected-(J49-Pada22)") (class "Default")
      (node (ref "J49") (pin "a22") (pinfunction "a22_a22") (pintype "bidirectional"))
    )
    (net (code "203") (name "unconnected-(J49-Pada23)") (class "Default")
      (node (ref "J49") (pin "a23") (pinfunction "a23_a23") (pintype "bidirectional"))
    )
    (net (code "204") (name "unconnected-(J49-Pada24)") (class "Default")
      (node (ref "J49") (pin "a24") (pinfunction "a24_a24") (pintype "bidirectional"))
    )
    (net (code "205") (name "unconnected-(J49-Pada25)") (class "Default")
      (node (ref "J49") (pin "a25") (pinfunction "a25_a25") (pintype "bidirectional"))
    )
    (net (code "206") (name "unconnected-(J49-Pada26)") (class "Default")
      (node (ref "J49") (pin "a26") (pinfunction "a26_a26") (pintype "bidirectional"))
    )
    (net (code "207") (name "unconnected-(J49-Pada27)") (class "Default")
      (node (ref "J49") (pin "a27") (pinfunction "a27_a27") (pintype "bidirectional"))
    )
    (net (code "208") (name "unconnected-(J49-Pada28)") (class "Default")
      (node (ref "J49") (pin "a28") (pinfunction "a28_a28") (pintype "bidirectional"))
    )
    (net (code "209") (name "unconnected-(J49-Pada29)") (class "Default")
      (node (ref "J49") (pin "a29") (pinfunction "a29_a29") (pintype "bidirectional"))
    )
    (net (code "210") (name "unconnected-(J49-Pada30)") (class "Default")
      (node (ref "J49") (pin "a30") (pinfunction "a30_a30") (pintype "bidirectional"))
    )
    (net (code "211") (name "unconnected-(J49-Pada31)") (class "Default")
      (node (ref "J49") (pin "a31") (pinfunction "a31_a31") (pintype "bidirectional"))
    )
    (net (code "212") (name "unconnected-(J49-Padb1)") (class "Default")
      (node (ref "J49") (pin "b1") (pinfunction "b1_b1") (pintype "bidirectional"))
    )
    (net (code "213") (name "unconnected-(J49-Padb3)") (class "Default")
      (node (ref "J49") (pin "b3") (pinfunction "b3_b3") (pintype "bidirectional"))
    )
    (net (code "214") (name "unconnected-(J49-Padb4)") (class "Default")
      (node (ref "J49") (pin "b4") (pinfunction "b4_b4") (pintype "bidirectional"))
    )
    (net (code "215") (name "unconnected-(J49-Padb5)") (class "Default")
      (node (ref "J49") (pin "b5") (pinfunction "b5_b5") (pintype "bidirectional"))
    )
    (net (code "216") (name "unconnected-(J49-Padb6)") (class "Default")
      (node (ref "J49") (pin "b6") (pinfunction "b6_b6") (pintype "bidirectional"))
    )
    (net (code "217") (name "unconnected-(J49-Padb7)") (class "Default")
      (node (ref "J49") (pin "b7") (pinfunction "b7_b7") (pintype "bidirectional"))
    )
    (net (code "218") (name "unconnected-(J49-Padb8)") (class "Default")
      (node (ref "J49") (pin "b8") (pinfunction "b8_b8") (pintype "bidirectional"))
    )
    (net (code "219") (name "unconnected-(J49-Padb9)") (class "Default")
      (node (ref "J49") (pin "b9") (pinfunction "b9_b9") (pintype "bidirectional"))
    )
    (net (code "220") (name "unconnected-(J49-Padb10)") (class "Default")
      (node (ref "J49") (pin "b10") (pinfunction "b10_b10") (pintype "bidirectional"))
    )
    (net (code "221") (name "unconnected-(J49-Padb11)") (class "Default")
      (node (ref "J49") (pin "b11") (pinfunction "b11_b11") (pintype "bidirectional"))
    )
    (net (code "222") (name "unconnected-(J49-Padb13)") (class "Default")
      (node (ref "J49") (pin "b13") (pinfunction "b13_b13") (pintype "bidirectional"))
    )
    (net (code "223") (name "unconnected-(J49-Padb14)") (class "Default")
      (node (ref "J49") (pin "b14") (pinfunction "b14_b14") (pintype "bidirectional"))
    )
    (net (code "224") (name "unconnected-(J49-Padb15)") (class "Default")
      (node (ref "J49") (pin "b15") (pinfunction "b15_b15") (pintype "bidirectional"))
    )
    (net (code "225") (name "unconnected-(J49-Padb16)") (class "Default")
      (node (ref "J49") (pin "b16") (pinfunction "b16_b16") (pintype "bidirectional"))
    )
    (net (code "226") (name "unconnected-(J49-Padb17)") (class "Default")
      (node (ref "J49") (pin "b17") (pinfunction "b17_b17") (pintype "bidirectional"))
    )
    (net (code "227") (name "unconnected-(J49-Padb18)") (class "Default")
      (node (ref "J49") (pin "b18") (pinfunction "b18_b18") (pintype "bidirectional"))
    )
    (net (code "228") (name "unconnected-(J49-Padb19)") (class "Default")
      (node (ref "J49") (pin "b19") (pinfunction "b19_b19") (pintype "bidirectional"))
    )
    (net (code "229") (name "unconnected-(J49-Padb21)") (class "Default")
      (node (ref "J49") (pin "b21") (pinfunction "b21_b21") (pintype "bidirectional"))
    )
    (net (code "230") (name "unconnected-(J49-Padb24)") (class "Default")
      (node (ref "J49") (pin "b24") (pinfunction "b24_b24") (pintype "bidirectional"))
    )
    (net (code "231") (name "unconnected-(J49-Padb25)") (class "Default")
      (node (ref "J49") (pin "b25") (pinfunction "b25_b25") (pintype "bidirectional"))
    )
    (net (code "232") (name "unconnected-(J49-Padb26)") (class "Default")
      (node (ref "J49") (pin "b26") (pinfunction "b26_b26") (pintype "bidirectional"))
    )
    (net (code "233") (name "unconnected-(J49-Padb27)") (class "Default")
      (node (ref "J49") (pin "b27") (pinfunction "b27_b27") (pintype "bidirectional"))
    )
    (net (code "234") (name "unconnected-(J49-Padb28)") (class "Default")
      (node (ref "J49") (pin "b28") (pinfunction "b28_b28") (pintype "bidirectional"))
    )
    (net (code "235") (name "unconnected-(J49-Padb29)") (class "Default")
      (node (ref "J49") (pin "b29") (pinfunction "b29_b29") (pintype "bidirectional"))
    )
    (net (code "236") (name "unconnected-(J49-Padb30)") (class "Default")
      (node (ref "J49") (pin "b30") (pinfunction "b30_b30") (pintype "bidirectional"))
    )
    (net (code "237") (name "unconnected-(J49-Padc1)") (class "Default")
      (node (ref "J49") (pin "c1") (pinfunction "c1_c1") (pintype "bidirectional"))
    )
    (net (code "238") (name "unconnected-(J49-Padc2)") (class "Default")
      (node (ref "J49") (pin "c2") (pinfunction "c2_c2") (pintype "bidirectional"))
    )
    (net (code "239") (name "unconnected-(J49-Padc3)") (class "Default")
      (node (ref "J49") (pin "c3") (pinfunction "c3_c3") (pintype "bidirectional"))
    )
    (net (code "240") (name "unconnected-(J49-Padc4)") (class "Default")
      (node (ref "J49") (pin "c4") (pinfunction "c4_c4") (pintype "bidirectional"))
    )
    (net (code "241") (name "unconnected-(J49-Padc5)") (class "Default")
      (node (ref "J49") (pin "c5") (pinfunction "c5_c5") (pintype "bidirectional"))
    )
    (net (code "242") (name "unconnected-(J49-Padc6)") (class "Default")
      (node (ref "J49") (pin "c6") (pinfunction "c6_c6") (pintype "bidirectional"))
    )
    (net (code "243") (name "unconnected-(J49-Padc7)") (class "Default")
      (node (ref "J49") (pin "c7") (pinfunction "c7_c7") (pintype "bidirectional"))
    )
    (net (code "244") (name "unconnected-(J49-Padc8)") (class "Default")
      (node (ref "J49") (pin "c8") (pinfunction "c8_c8") (pintype "bidirectional"))
    )
    (net (code "245") (name "unconnected-(J49-Padc10)") (class "Default")
      (node (ref "J49") (pin "c10") (pinfunction "c10_c10") (pintype "bidirectional"))
    )
    (net (code "246") (name "unconnected-(J49-Padc11)") (class "Default")
      (node (ref "J49") (pin "c11") (pinfunction "c11_c11") (pintype "bidirectional"))
    )
    (net (code "247") (name "unconnected-(J49-Padc12)") (class "Default")
      (node (ref "J49") (pin "c12") (pinfunction "c12_c12") (pintype "bidirectional"))
    )
    (net (code "248") (name "unconnected-(J49-Padc13)") (class "Default")
      (node (ref "J49") (pin "c13") (pinfunction "c13_c13") (pintype "bidirectional"))
    )
    (net (code "249") (name "unconnected-(J49-Padc14)") (class "Default")
      (node (ref "J49") (pin "c14") (pinfunction "c14_c14") (pintype "bidirectional"))
    )
    (net (code "250") (name "unconnected-(J49-Padc15)") (class "Default")
      (node (ref "J49") (pin "c15") (pinfunction "c15_c15") (pintype "bidirectional"))
    )
    (net (code "251") (name "unconnected-(J49-Padc16)") (class "Default")
      (node (ref "J49") (pin "c16") (pinfunction "c16_c16") (pintype "bidirectional"))
    )
    (net (code "252") (name "unconnected-(J49-Padc17)") (class "Default")
      (node (ref "J49") (pin "c17") (pinfunction "c17_c17") (pintype "bidirectional"))
    )
    (net (code "253") (name "unconnected-(J49-Padc18)") (class "Default")
      (node (ref "J49") (pin "c18") (pinfunction "c18_c18") (pintype "bidirectional"))
    )
    (net (code "254") (name "unconnected-(J49-Padc19)") (class "Default")
      (node (ref "J49") (pin "c19") (pinfunction "c19_c19") (pintype "bidirectional"))
    )
    (net (code "255") (name "unconnected-(J49-Padc20)") (class "Default")
      (node (ref "J49") (pin "c20") (pinfunction "c20_c20") (pintype "bidirectional"))
    )
    (net (code "256") (name "unconnected-(J49-Padc21)") (class "Default")
      (node (ref "J49") (pin "c21") (pinfunction "c21_c21") (pintype "bidirectional"))
    )
    (net (code "257") (name "unconnected-(J49-Padc22)") (class "Default")
      (node (ref "J49") (pin "c22") (pinfunction "c22_c22") (pintype "bidirectional"))
    )
    (net (code "258") (name "unconnected-(J49-Padc23)") (class "Default")
      (node (ref "J49") (pin "c23") (pinfunction "c23_c23") (pintype "bidirectional"))
    )
    (net (code "259") (name "unconnected-(J49-Padc24)") (class "Default")
      (node (ref "J49") (pin "c24") (pinfunction "c24_c24") (pintype "bidirectional"))
    )
    (net (code "260") (name "unconnected-(J49-Padc25)") (class "Default")
      (node (ref "J49") (pin "c25") (pinfunction "c25_c25") (pintype "bidirectional"))
    )
    (net (code "261") (name "unconnected-(J49-Padc26)") (class "Default")
      (node (ref "J49") (pin "c26") (pinfunction "c26_c26") (pintype "bidirectional"))
    )
    (net (code "262") (name "unconnected-(J49-Padc27)") (class "Default")
      (node (ref "J49") (pin "c27") (pinfunction "c27_c27") (pintype "bidirectional"))
    )
    (net (code "263") (name "unconnected-(J49-Padc28)") (class "Default")
      (node (ref "J49") (pin "c28") (pinfunction "c28_c28") (pintype "bidirectional"))
    )
    (net (code "264") (name "unconnected-(J49-Padc29)") (class "Default")
      (node (ref "J49") (pin "c29") (pinfunction "c29_c29") (pintype "bidirectional"))
    )
    (net (code "265") (name "unconnected-(J49-Padc30)") (class "Default")
      (node (ref "J49") (pin "c30") (pinfunction "c30_c30") (pintype "bidirectional"))
    )
  )
)
